# Schematic.net
KiCad netlist of a schematic drawn in Altium Designer
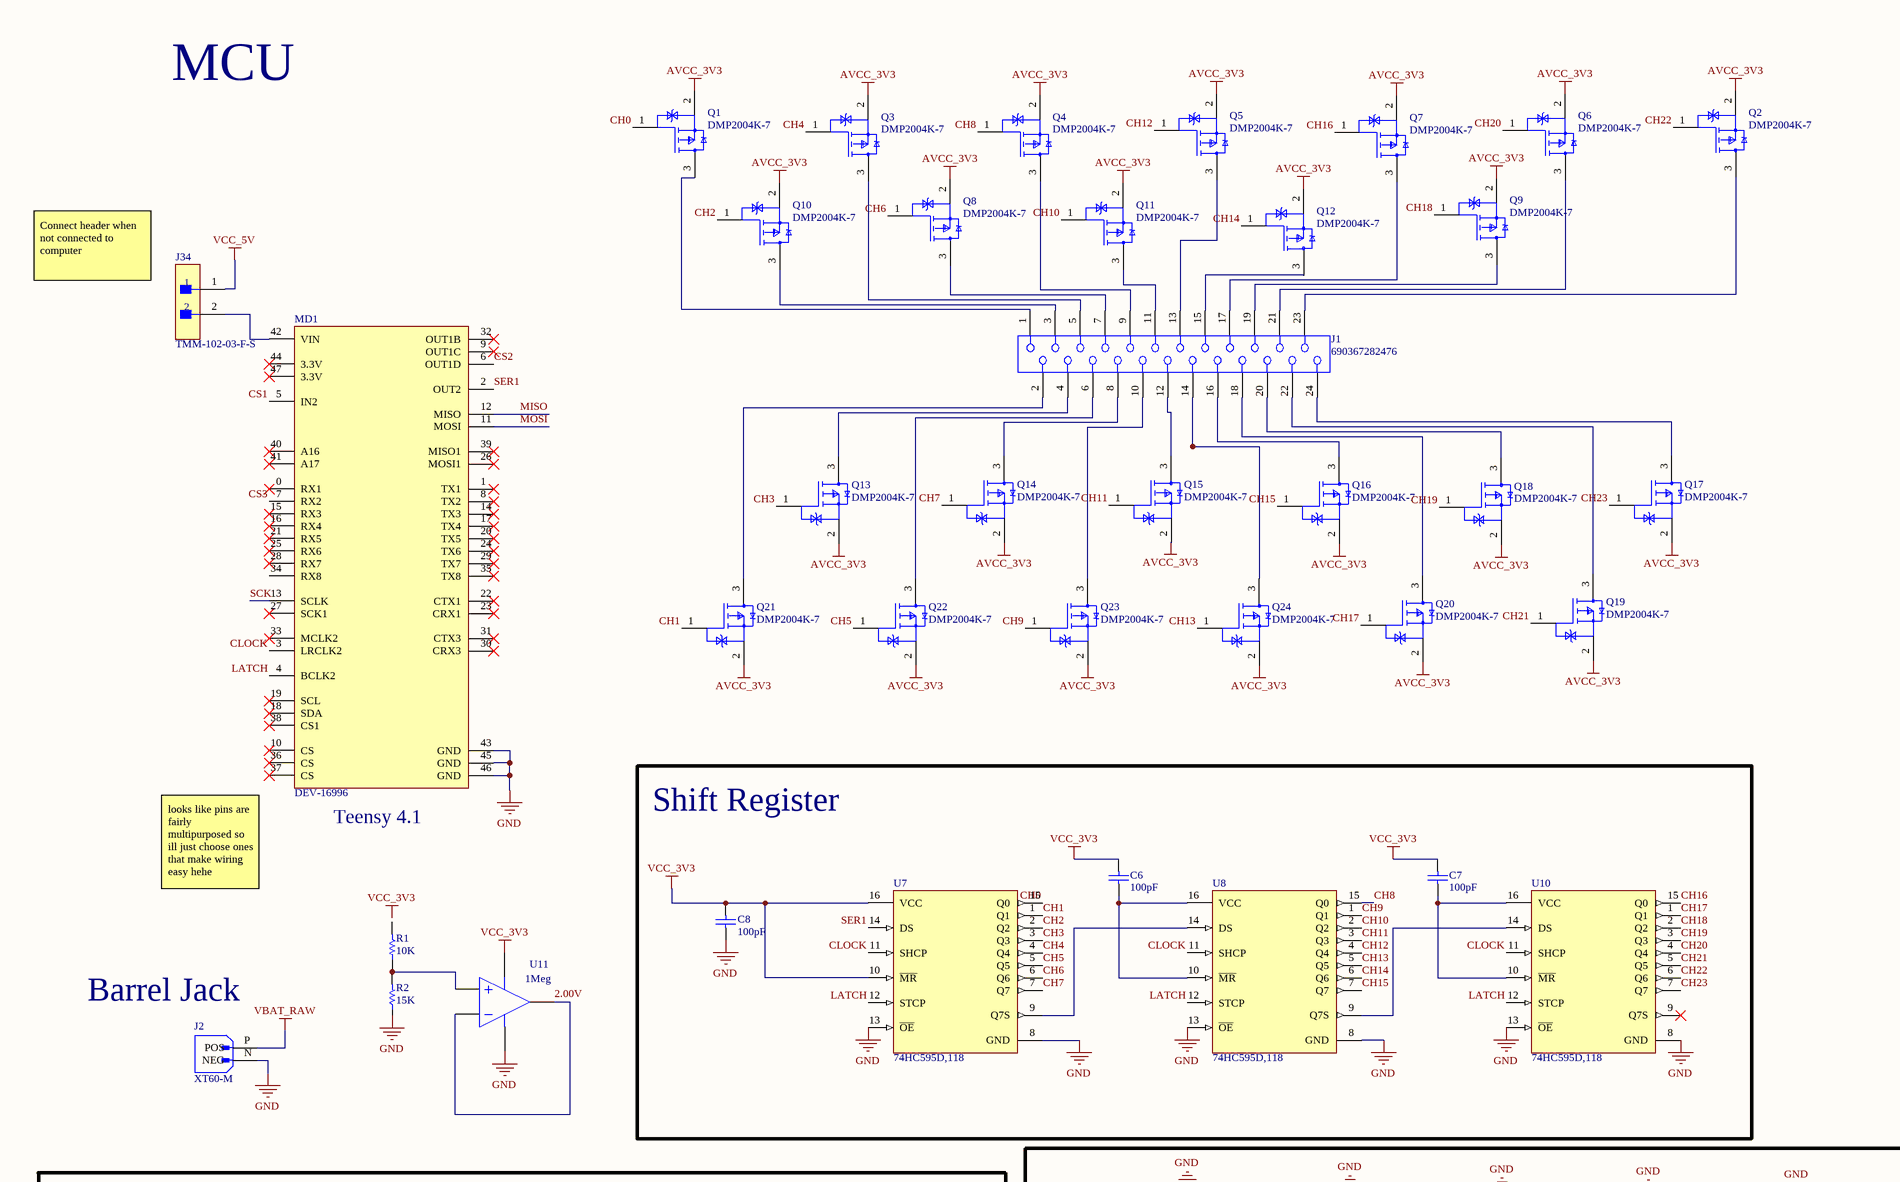
[diagram p0: Schematic.SchDoc, top left]
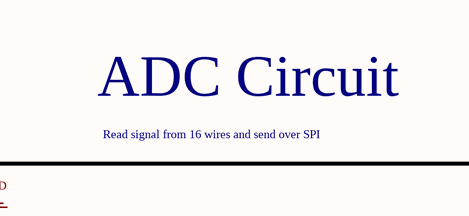
[diagram p1: Schematic.SchDoc, top right]
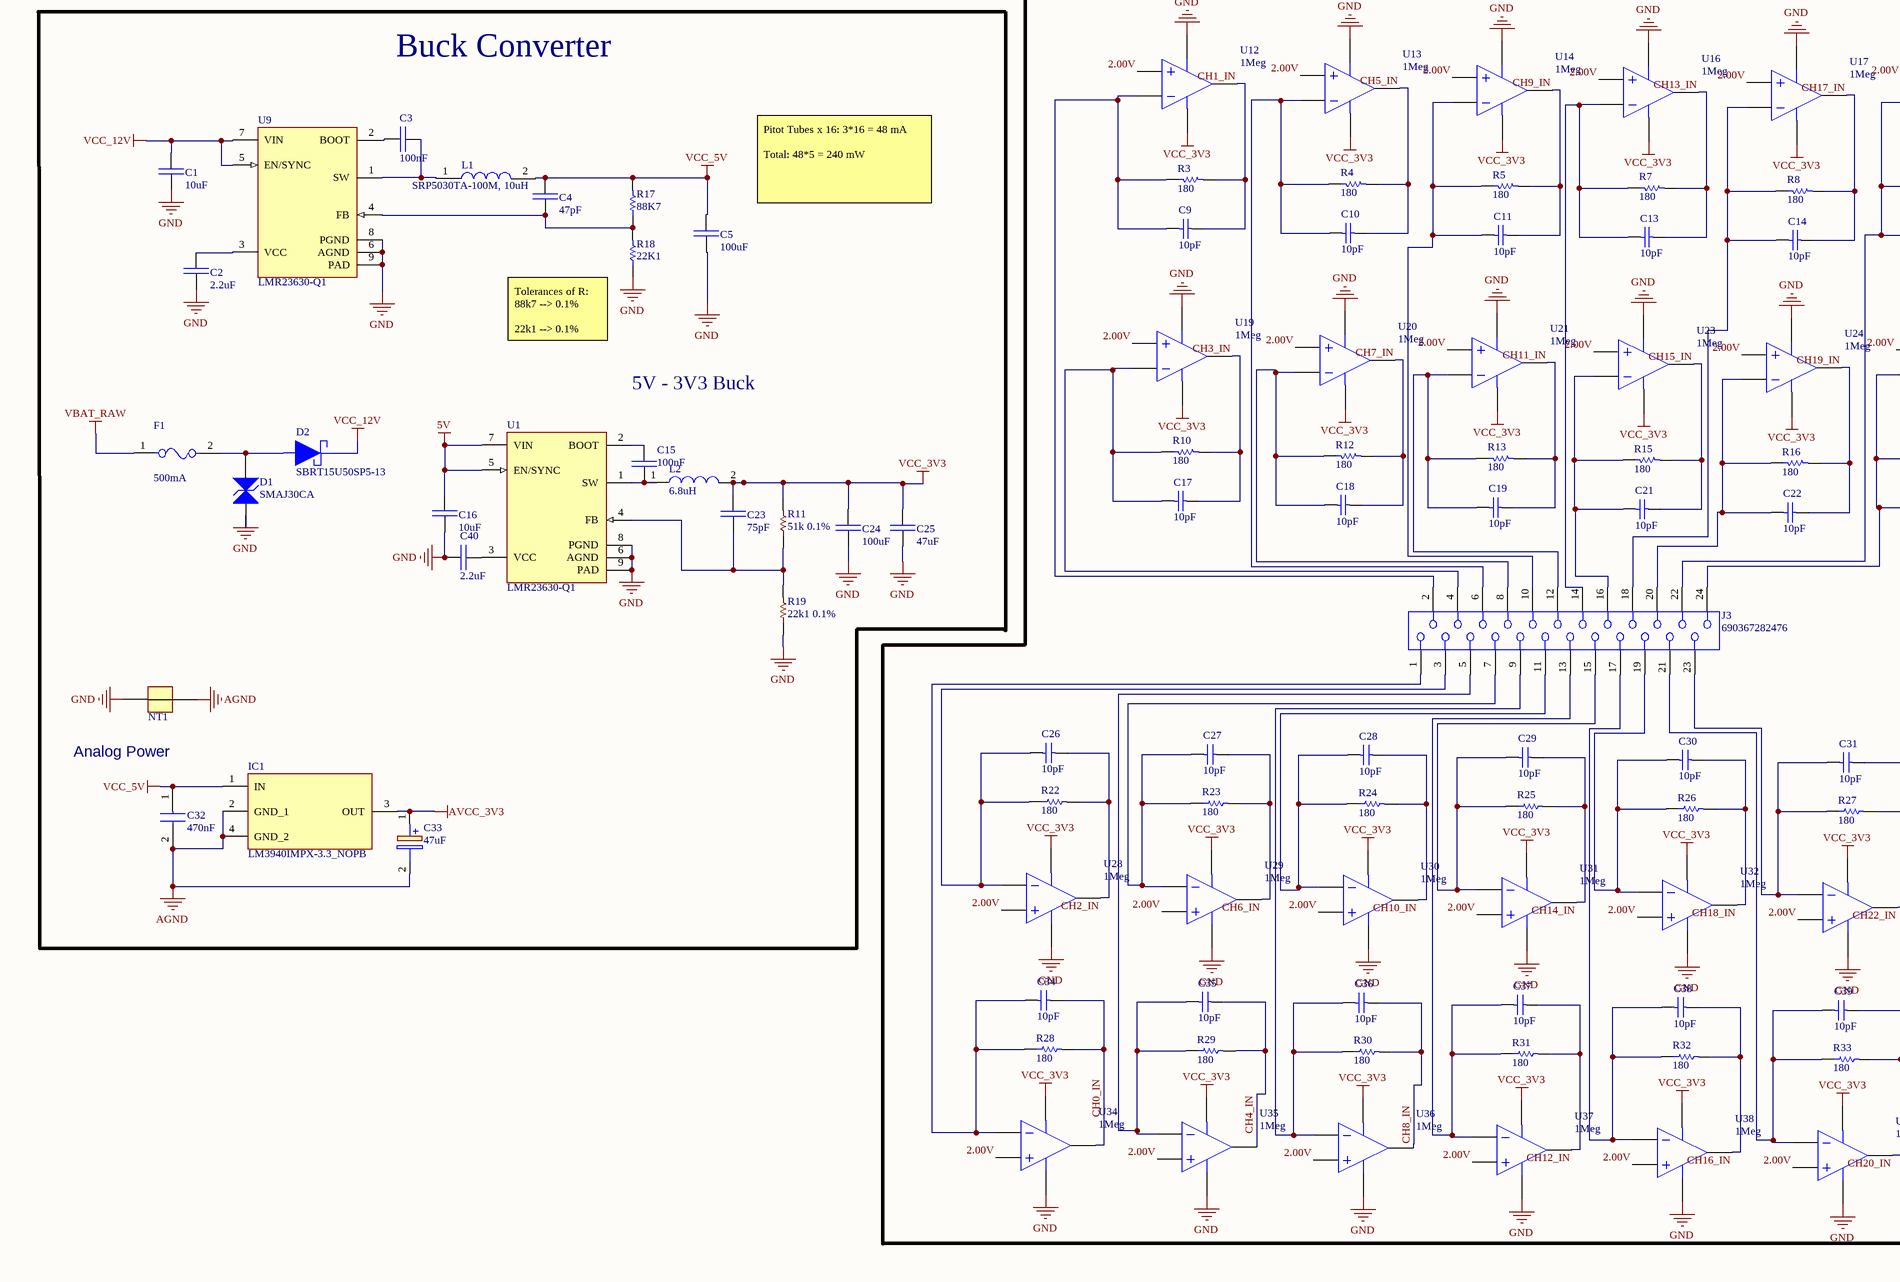
[diagram p2: Schematic.SchDoc, bottom left]
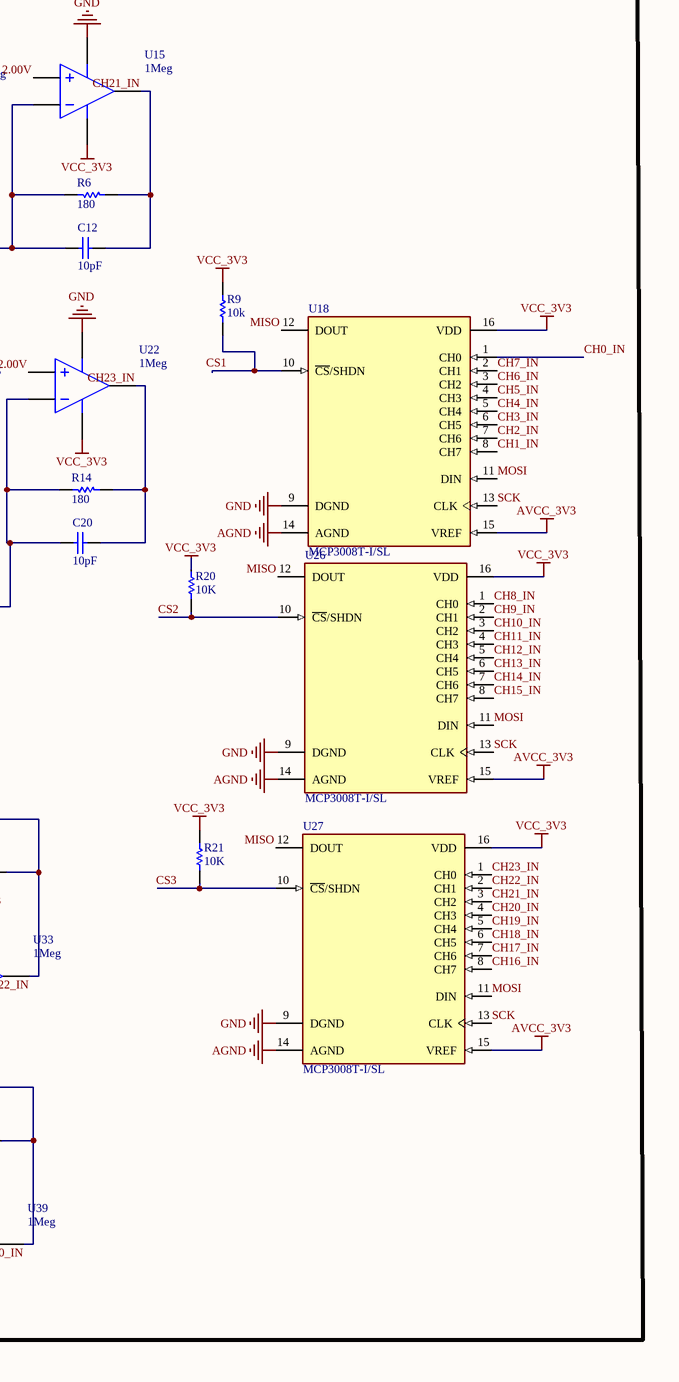
[diagram p3: Schematic.SchDoc, bottom right]

(export (version "E")
  (design (tool "Eeschema 10.0.6"))
  (components
    (comp (ref "C1")
      (value "10uF")
      (footprint "CAP_SM0603_YAGEOCC2_N")
      (fields
        (field (name "MANUFACTURER") "Murata")
        (field (name "MANUFACTURER PART NUMBER") "GRM188R6YA106MA73D")
      )
      (libsource (lib "ResistorCapsInductors") (part "GRM188R6YA106MA73D"))
    )
    (comp (ref "C2")
      (value "2.2uF")
      (footprint "CAP_SM0603_YAGEOCC2_N")
      (description "CAP CER 2.2UF 25V X5R 0603")
      (fields
        (field (name "MANUFACTURER") "Yageo")
        (field (name "MANUFACTURER PART NUMBER") "CC0603KRX7R9BB183")
      )
      (libsource (lib "ResistorCapsInductors") (part "CC0603KRX5R8BB225"))
    )
    (comp (ref "C3")
      (value "100nF")
      (footprint "CAP_SM0603_YAGEOCC2_N")
      (description "CAP 100nF SM0603 X7R 50V YAGEO CC2")
      (fields
        (field (name "MANUFACTURER") "Yageo")
        (field (name "MANUFACTURER PART NUMBER") "CC0603KRX7R9BB104")
      )
      (libsource (lib "ResistorCapsInductors") (part "CC0603KRX7R9BB104"))
    )
    (comp (ref "C4")
      (value "47pF")
      (footprint "CAP_SM0603_YAGEOCC2_N")
      (description "CAP 47pF SM0603 NPO 50V YAGEO CC2")
      (fields
        (field (name "MANUFACTURER") "Yageo")
        (field (name "MANUFACTURER PART NUMBER") "CC0603JRNPO9BN470")
      )
      (libsource (lib "ResistorCapsInductors") (part "CC0603JRNPO9BN470"))
    )
    (comp (ref "C5")
      (value "100uF")
      (footprint "FP-GRM31C-0_3-e0_3_0_8-IPC_A")
      (fields
        (field (name "MANUFACTURER") "Murata")
        (field (name "MANUFACTURER PART NUMBER") "GRM31CR61A107MEA8L")
      )
      (libsource (lib "ResistorCapsInductors") (part "GRM31CR61A107MEA8L"))
    )
    (comp (ref "C6")
      (value "100pF")
      (footprint "CAPC2013X140X50LL20T25")
      (fields
        (field (name "PART NUMBER") "0805ZC105KAZ2A")
        (field (name "MANUFACTURER") "AVX Interconnect / Elco")
      )
      (libsource (lib "Altium Content Vault") (part "CAP"))
    )
    (comp (ref "C7")
      (value "100pF")
      (footprint "CAPC2013X140X50LL20T25")
      (fields
        (field (name "PART NUMBER") "0805ZC105KAZ2A")
        (field (name "MANUFACTURER") "AVX Interconnect / Elco")
      )
      (libsource (lib "Altium Content Vault") (part "CAP"))
    )
    (comp (ref "C8")
      (value "100pF")
      (footprint "CAPC2013X140X50LL20T25")
      (fields
        (field (name "PART NUMBER") "0805ZC105KAZ2A")
        (field (name "MANUFACTURER") "AVX Interconnect / Elco")
      )
      (libsource (lib "Altium Content Vault") (part "CAP"))
    )
    (comp (ref "C9")
      (value "10pF")
      (footprint "CAP_R15_JOD")
      (description "Capacitor")
      (libsource (lib "Simulation Generic Components") (part "Capacitor"))
    )
    (comp (ref "C10")
      (value "10pF")
      (footprint "CAP_R15_JOD")
      (description "Capacitor")
      (libsource (lib "Simulation Generic Components") (part "Capacitor"))
    )
    (comp (ref "C11")
      (value "10pF")
      (footprint "CAP_R15_JOD")
      (description "Capacitor")
      (libsource (lib "Simulation Generic Components") (part "Capacitor"))
    )
    (comp (ref "C12")
      (value "10pF")
      (footprint "CAP_R15_JOD")
      (description "Capacitor")
      (libsource (lib "Simulation Generic Components") (part "Capacitor"))
    )
    (comp (ref "C13")
      (value "10pF")
      (footprint "CAP_R15_JOD")
      (description "Capacitor")
      (libsource (lib "Simulation Generic Components") (part "Capacitor"))
    )
    (comp (ref "C14")
      (value "10pF")
      (footprint "CAP_R15_JOD")
      (description "Capacitor")
      (libsource (lib "Simulation Generic Components") (part "Capacitor"))
    )
    (comp (ref "C15")
      (value "100nF")
      (footprint "CAP_SM0603_YAGEOCC2_N")
      (description "CAP 100nF SM0603 X7R 50V YAGEO CC2")
      (fields
        (field (name "MANUFACTURER") "Yageo")
        (field (name "MANUFACTURER PART NUMBER") "CC0603KRX7R9BB104")
      )
      (libsource (lib "ResistorCapsInductors") (part "CC0603KRX7R9BB104"))
    )
    (comp (ref "C16")
      (value "10uF")
      (footprint "CAP_SM0603_YAGEOCC2_N")
      (fields
        (field (name "MANUFACTURER") "Murata")
        (field (name "MANUFACTURER PART NUMBER") "GRM188R6YA106MA73D")
      )
      (libsource (lib "ResistorCapsInductors") (part "GRM188R6YA106MA73D"))
    )
    (comp (ref "C17")
      (value "10pF")
      (footprint "CAP_R15_JOD")
      (description "Capacitor")
      (libsource (lib "Simulation Generic Components") (part "Capacitor"))
    )
    (comp (ref "C18")
      (value "10pF")
      (footprint "CAP_R15_JOD")
      (description "Capacitor")
      (libsource (lib "Simulation Generic Components") (part "Capacitor"))
    )
    (comp (ref "C19")
      (value "10pF")
      (footprint "CAP_R15_JOD")
      (description "Capacitor")
      (libsource (lib "Simulation Generic Components") (part "Capacitor"))
    )
    (comp (ref "C20")
      (value "10pF")
      (footprint "CAP_R15_JOD")
      (description "Capacitor")
      (libsource (lib "Simulation Generic Components") (part "Capacitor"))
    )
    (comp (ref "C21")
      (value "10pF")
      (footprint "CAP_R15_JOD")
      (description "Capacitor")
      (libsource (lib "Simulation Generic Components") (part "Capacitor"))
    )
    (comp (ref "C22")
      (value "10pF")
      (footprint "CAP_R15_JOD")
      (description "Capacitor")
      (libsource (lib "Simulation Generic Components") (part "Capacitor"))
    )
    (comp (ref "C23")
      (value "75pF")
      (footprint "CAP_SM0603_YAGEOCC2_N")
      (description "CAP 75pF SM0603 NPO 50V YAGEO CC2")
      (fields
        (field (name "MANUFACTURER") "Yageo")
        (field (name "MANUFACTURER PART NUMBER") "CC0603JRNPO9BN820")
      )
      (libsource (lib "ResistorCapsInductors") (part "CC0603JRNPO9BN750"))
    )
    (comp (ref "C24")
      (value "100uF")
      (footprint "FP-GRM31C-0_3-e0_3_0_8-IPC_A")
      (fields
        (field (name "MANUFACTURER") "Murata")
        (field (name "MANUFACTURER PART NUMBER") "GRM31CR61A107MEA8L")
      )
      (libsource (lib "ResistorCapsInductors") (part "GRM31CR61A107MEA8L"))
    )
    (comp (ref "C25")
      (value "47uF")
      (footprint "CAP_SM0603_YAGEOCC2_N")
      (description "CAP 47uF SM0603 X5R 4V YAGEO CC2")
      (fields
        (field (name "MANUFACTURER") "Yageo")
        (field (name "MANUFACTURER PART NUMBER") "CC0603KRX7R9BB223")
      )
      (libsource (lib "ResistorCapsInductors") (part "CC0603MRX5R4BB476"))
    )
    (comp (ref "C26")
      (value "10pF")
      (footprint "CAP_R15_JOD")
      (description "Capacitor")
      (libsource (lib "Simulation Generic Components") (part "Capacitor"))
    )
    (comp (ref "C27")
      (value "10pF")
      (footprint "CAP_R15_JOD")
      (description "Capacitor")
      (libsource (lib "Simulation Generic Components") (part "Capacitor"))
    )
    (comp (ref "C28")
      (value "10pF")
      (footprint "CAP_R15_JOD")
      (description "Capacitor")
      (libsource (lib "Simulation Generic Components") (part "Capacitor"))
    )
    (comp (ref "C29")
      (value "10pF")
      (footprint "CAP_R15_JOD")
      (description "Capacitor")
      (libsource (lib "Simulation Generic Components") (part "Capacitor"))
    )
    (comp (ref "C30")
      (value "10pF")
      (footprint "CAP_R15_JOD")
      (description "Capacitor")
      (libsource (lib "Simulation Generic Components") (part "Capacitor"))
    )
    (comp (ref "C31")
      (value "10pF")
      (footprint "CAP_R15_JOD")
      (description "Capacitor")
      (libsource (lib "Simulation Generic Components") (part "Capacitor"))
    )
    (comp (ref "C32")
      (value "470nF")
      (footprint "CAPC1608X90N")
      (description "SMD/SMT CGA 0603 50V 0.47uF X7R 10% AEC-Q200")
      (fields
        (field (name "MANUFACTURER_PART_NUMBER") "CGA3E3X7R1H474K080AB")
        (field (name "MOUSER PART NUMBER") "810-CGA3E3X7R1H474KB")
      )
      (libsource (lib "ResistorCapsInductors") (part "CGA3E3X7R1H474K080AB"))
    )
    (comp (ref "C33")
      (value "47uF")
      (footprint "CAPPM3216X180N")
      (description "47uF 10V Tantalum Capacitor For LM3940IMPX-3.3_NOPB LDO")
      (fields
        (field (name "MANUFACTURER_PART_NUMBER") "TLJA476M010R0600")
        (field (name "MOUSER PART NUMBER") "581-TLJA476M010R0600")
      )
      (libsource (lib "ResistorCapsInductors") (part "TLJA476M010R0600"))
    )
    (comp (ref "C34")
      (value "10pF")
      (footprint "CAP_R15_JOD")
      (description "Capacitor")
      (libsource (lib "Simulation Generic Components") (part "Capacitor"))
    )
    (comp (ref "C35")
      (value "10pF")
      (footprint "CAP_R15_JOD")
      (description "Capacitor")
      (libsource (lib "Simulation Generic Components") (part "Capacitor"))
    )
    (comp (ref "C36")
      (value "10pF")
      (footprint "CAP_R15_JOD")
      (description "Capacitor")
      (libsource (lib "Simulation Generic Components") (part "Capacitor"))
    )
    (comp (ref "C37")
      (value "10pF")
      (footprint "CAP_R15_JOD")
      (description "Capacitor")
      (libsource (lib "Simulation Generic Components") (part "Capacitor"))
    )
    (comp (ref "C38")
      (value "10pF")
      (footprint "CAP_R15_JOD")
      (description "Capacitor")
      (libsource (lib "Simulation Generic Components") (part "Capacitor"))
    )
    (comp (ref "C39")
      (value "10pF")
      (footprint "CAP_R15_JOD")
      (description "Capacitor")
      (libsource (lib "Simulation Generic Components") (part "Capacitor"))
    )
    (comp (ref "C40")
      (value "2.2uF")
      (footprint "CAP_SM0603_YAGEOCC2_N")
      (description "CAP CER 2.2UF 25V X5R 0603")
      (fields
        (field (name "MANUFACTURER") "Yageo")
        (field (name "MANUFACTURER PART NUMBER") "CC0603KRX7R9BB183")
      )
      (libsource (lib "ResistorCapsInductors") (part "CC0603KRX5R8BB225"))
    )
    (comp (ref "D1")
      (value "SMAJ30CA")
      (footprint "LFUS-DO-214AC-A-2_V")
      (description "Transient Voltage Suppression Diode, 30 V, -65 to 150 degC, 2-Pin SMD, RoHS, Tape and Reel")
      (fields (field (name "MANUFACTURER") "Littelfuse"))
      (libsource (lib "DiodesAndFuses") (part "SMAJ30CA"))
    )
    (comp (ref "D2")
      (value "SBRT15U50SP5-13")
      (footprint "SBRT15U50SP5-13")
      (description "Reverse Polarity Protection")
      (fields (field (name "MANUFACTURER") "Diodes Incorporated"))
      (libsource (lib "DiodesAndFuses") (part "SBRT15U50SP5-13"))
    )
    (comp (ref "F1")
      (value "500mA")
      (footprint "FP-SF-0603S-MFG")
      (description "FUSE BOARD MNT 500MA 50VDC 0603")
      (fields
        (field (name "MANUFACTURER") "Bourns Inc.")
        (field (name "MANUFACTURER PART NUMBER") "SF-0603S050-2")
      )
      (libsource (lib "Altium Content Vault") (part "5bcf9b9f640e542cf0359d10258e979"))
    )
    (comp (ref "IC1")
      (value "LM3940IMPX-3.3_NOPB")
      (footprint "SOT230P700X180-4N")
      (description "3V3 LDO")
      (fields
        (field (name "MANUFACTURER_PART_NUMBER") "LM3940IMPX-3.3/NOPB")
        (field (name "MOUSER PART NUMBER") "926-LM3940IMPX33NOPB")
      )
      (libsource (lib "Power") (part "LM3940IMPX-3.3_NOPB"))
    )
    (comp (ref "J1")
      (value "690367282476")
      (footprint "FPC-SMD_24P-P0.50_05A20L24P")
      (libsource (lib "CustomParts") (part "CMP-1502-00827-2"))
    )
    (comp (ref "J2")
      (value "XT60-M")
      (footprint "AMASS_XT60-M")
      (description "Plug; DC supply; XT60; male; PIN: 2; for cable; soldered; 30A; 500V")
      (fields (field (name "MF") "AMASS"))
      (libsource (lib "XT60-M") (part "XT60-M"))
    )
    (comp (ref "J3")
      (value "690367282476")
      (footprint "FPC-SMD_24P-P0.50_05A20L24P")
      (libsource (lib "CustomParts") (part "CMP-1502-00827-2"))
    )
    (comp (ref "J34")
      (value "TMM-102-03-F-S")
      (footprint "FP-TMM-102-03-F-S-MFG")
      (description "CONN HEADER VERT 2POS 2MM")
      (libsource (lib "Altium Content Vault") (part "3bc925449376181038e59eaffc5286c"))
    )
    (comp (ref "L1")
      (value "SRP5030TA-100M, 10uH")
      (footprint "INDPM5752X300N")
      (description "10 uH Inductor")
      (fields
        (field (name "MANUFACTURER_PART_NUMBER") "SRP5030TA-100M")
        (field (name "MOUSER PART NUMBER") "652-SRP5030TA-100M")
      )
      (libsource (lib "ResistorCapsInductors") (part "SRP5030TA-100M"))
    )
    (comp (ref "L2")
      (value "6.8uH")
      (footprint "INDPM5752X300N")
      (description "6.8uH Inductor")
      (fields
        (field (name "MANUFACTURER_PART_NUMBER") "SRP5030TA-6R8M")
        (field (name "MOUSER PART NUMBER") "652-SRP5030TA-6R8M")
      )
      (libsource (lib "ResistorCapsInductors") (part "SRP5030TA-6R8M"))
    )
    (comp (ref "MD1")
      (value "DEV-16996")
      (footprint "FP-DEV-16996-MFG")
      (description "TEENSY 4.1 (HEADERS)")
      (libsource (lib "Altium Content Vault") (part "080115a1ce54750370cf87ec145ee29"))
    )
    (comp (ref "NT1")
      (value "Net Tie")
      (footprint "Net_Tie_80mil")
      (description "Use to tie together nets")
      (libsource (lib "Misc") (part "Net Tie"))
    )
    (comp (ref "Q1")
      (value "DMP2004K-7")
      (footprint "FP-SOT23-MFG")
      (description "MOSFET P-CH 20V 600MA SOT23-3")
      (fields
        (field (name "OCTOPART") "https://octopart.com/dmp2004k-7-diodes+inc.-7151877")
        (field (name "MANUFACTURER") "Diodes Inc.")
      )
      (libsource (lib "Altium Content Vault") (part "0909edbb8d389a8e80b8543cd1a9d7a"))
    )
    (comp (ref "Q2")
      (value "DMP2004K-7")
      (footprint "FP-SOT23-MFG")
      (description "MOSFET P-CH 20V 600MA SOT23-3")
      (fields
        (field (name "OCTOPART") "https://octopart.com/dmp2004k-7-diodes+inc.-7151877")
        (field (name "MANUFACTURER") "Diodes Inc.")
      )
      (libsource (lib "Altium Content Vault") (part "0909edbb8d389a8e80b8543cd1a9d7a"))
    )
    (comp (ref "Q3")
      (value "DMP2004K-7")
      (footprint "FP-SOT23-MFG")
      (description "MOSFET P-CH 20V 600MA SOT23-3")
      (fields
        (field (name "OCTOPART") "https://octopart.com/dmp2004k-7-diodes+inc.-7151877")
        (field (name "MANUFACTURER") "Diodes Inc.")
      )
      (libsource (lib "Altium Content Vault") (part "0909edbb8d389a8e80b8543cd1a9d7a"))
    )
    (comp (ref "Q4")
      (value "DMP2004K-7")
      (footprint "FP-SOT23-MFG")
      (description "MOSFET P-CH 20V 600MA SOT23-3")
      (fields
        (field (name "OCTOPART") "https://octopart.com/dmp2004k-7-diodes+inc.-7151877")
        (field (name "MANUFACTURER") "Diodes Inc.")
      )
      (libsource (lib "Altium Content Vault") (part "0909edbb8d389a8e80b8543cd1a9d7a"))
    )
    (comp (ref "Q5")
      (value "DMP2004K-7")
      (footprint "FP-SOT23-MFG")
      (description "MOSFET P-CH 20V 600MA SOT23-3")
      (fields
        (field (name "OCTOPART") "https://octopart.com/dmp2004k-7-diodes+inc.-7151877")
        (field (name "MANUFACTURER") "Diodes Inc.")
      )
      (libsource (lib "Altium Content Vault") (part "0909edbb8d389a8e80b8543cd1a9d7a"))
    )
    (comp (ref "Q6")
      (value "DMP2004K-7")
      (footprint "FP-SOT23-MFG")
      (description "MOSFET P-CH 20V 600MA SOT23-3")
      (fields
        (field (name "OCTOPART") "https://octopart.com/dmp2004k-7-diodes+inc.-7151877")
        (field (name "MANUFACTURER") "Diodes Inc.")
      )
      (libsource (lib "Altium Content Vault") (part "0909edbb8d389a8e80b8543cd1a9d7a"))
    )
    (comp (ref "Q7")
      (value "DMP2004K-7")
      (footprint "FP-SOT23-MFG")
      (description "MOSFET P-CH 20V 600MA SOT23-3")
      (fields
        (field (name "OCTOPART") "https://octopart.com/dmp2004k-7-diodes+inc.-7151877")
        (field (name "MANUFACTURER") "Diodes Inc.")
      )
      (libsource (lib "Altium Content Vault") (part "0909edbb8d389a8e80b8543cd1a9d7a"))
    )
    (comp (ref "Q8")
      (value "DMP2004K-7")
      (footprint "FP-SOT23-MFG")
      (description "MOSFET P-CH 20V 600MA SOT23-3")
      (fields
        (field (name "OCTOPART") "https://octopart.com/dmp2004k-7-diodes+inc.-7151877")
        (field (name "MANUFACTURER") "Diodes Inc.")
      )
      (libsource (lib "Altium Content Vault") (part "0909edbb8d389a8e80b8543cd1a9d7a"))
    )
    (comp (ref "Q9")
      (value "DMP2004K-7")
      (footprint "FP-SOT23-MFG")
      (description "MOSFET P-CH 20V 600MA SOT23-3")
      (fields
        (field (name "OCTOPART") "https://octopart.com/dmp2004k-7-diodes+inc.-7151877")
        (field (name "MANUFACTURER") "Diodes Inc.")
      )
      (libsource (lib "Altium Content Vault") (part "0909edbb8d389a8e80b8543cd1a9d7a"))
    )
    (comp (ref "Q10")
      (value "DMP2004K-7")
      (footprint "FP-SOT23-MFG")
      (description "MOSFET P-CH 20V 600MA SOT23-3")
      (fields
        (field (name "OCTOPART") "https://octopart.com/dmp2004k-7-diodes+inc.-7151877")
        (field (name "MANUFACTURER") "Diodes Inc.")
      )
      (libsource (lib "Altium Content Vault") (part "0909edbb8d389a8e80b8543cd1a9d7a"))
    )
    (comp (ref "Q11")
      (value "DMP2004K-7")
      (footprint "FP-SOT23-MFG")
      (description "MOSFET P-CH 20V 600MA SOT23-3")
      (fields
        (field (name "OCTOPART") "https://octopart.com/dmp2004k-7-diodes+inc.-7151877")
        (field (name "MANUFACTURER") "Diodes Inc.")
      )
      (libsource (lib "Altium Content Vault") (part "0909edbb8d389a8e80b8543cd1a9d7a"))
    )
    (comp (ref "Q12")
      (value "DMP2004K-7")
      (footprint "FP-SOT23-MFG")
      (description "MOSFET P-CH 20V 600MA SOT23-3")
      (fields
        (field (name "OCTOPART") "https://octopart.com/dmp2004k-7-diodes+inc.-7151877")
        (field (name "MANUFACTURER") "Diodes Inc.")
      )
      (libsource (lib "Altium Content Vault") (part "0909edbb8d389a8e80b8543cd1a9d7a"))
    )
    (comp (ref "Q13")
      (value "DMP2004K-7")
      (footprint "FP-SOT23-MFG")
      (description "MOSFET P-CH 20V 600MA SOT23-3")
      (fields
        (field (name "OCTOPART") "https://octopart.com/dmp2004k-7-diodes+inc.-7151877")
        (field (name "MANUFACTURER") "Diodes Inc.")
      )
      (libsource (lib "Altium Content Vault") (part "0909edbb8d389a8e80b8543cd1a9d7a"))
    )
    (comp (ref "Q14")
      (value "DMP2004K-7")
      (footprint "FP-SOT23-MFG")
      (description "MOSFET P-CH 20V 600MA SOT23-3")
      (fields
        (field (name "OCTOPART") "https://octopart.com/dmp2004k-7-diodes+inc.-7151877")
        (field (name "MANUFACTURER") "Diodes Inc.")
      )
      (libsource (lib "Altium Content Vault") (part "0909edbb8d389a8e80b8543cd1a9d7a"))
    )
    (comp (ref "Q15")
      (value "DMP2004K-7")
      (footprint "FP-SOT23-MFG")
      (description "MOSFET P-CH 20V 600MA SOT23-3")
      (fields
        (field (name "OCTOPART") "https://octopart.com/dmp2004k-7-diodes+inc.-7151877")
        (field (name "MANUFACTURER") "Diodes Inc.")
      )
      (libsource (lib "Altium Content Vault") (part "0909edbb8d389a8e80b8543cd1a9d7a"))
    )
    (comp (ref "Q16")
      (value "DMP2004K-7")
      (footprint "FP-SOT23-MFG")
      (description "MOSFET P-CH 20V 600MA SOT23-3")
      (fields
        (field (name "OCTOPART") "https://octopart.com/dmp2004k-7-diodes+inc.-7151877")
        (field (name "MANUFACTURER") "Diodes Inc.")
      )
      (libsource (lib "Altium Content Vault") (part "0909edbb8d389a8e80b8543cd1a9d7a"))
    )
    (comp (ref "Q17")
      (value "DMP2004K-7")
      (footprint "FP-SOT23-MFG")
      (description "MOSFET P-CH 20V 600MA SOT23-3")
      (fields
        (field (name "OCTOPART") "https://octopart.com/dmp2004k-7-diodes+inc.-7151877")
        (field (name "MANUFACTURER") "Diodes Inc.")
      )
      (libsource (lib "Altium Content Vault") (part "0909edbb8d389a8e80b8543cd1a9d7a"))
    )
    (comp (ref "Q18")
      (value "DMP2004K-7")
      (footprint "FP-SOT23-MFG")
      (description "MOSFET P-CH 20V 600MA SOT23-3")
      (fields
        (field (name "OCTOPART") "https://octopart.com/dmp2004k-7-diodes+inc.-7151877")
        (field (name "MANUFACTURER") "Diodes Inc.")
      )
      (libsource (lib "Altium Content Vault") (part "0909edbb8d389a8e80b8543cd1a9d7a"))
    )
    (comp (ref "Q19")
      (value "DMP2004K-7")
      (footprint "FP-SOT23-MFG")
      (description "MOSFET P-CH 20V 600MA SOT23-3")
      (fields
        (field (name "OCTOPART") "https://octopart.com/dmp2004k-7-diodes+inc.-7151877")
        (field (name "MANUFACTURER") "Diodes Inc.")
      )
      (libsource (lib "Altium Content Vault") (part "0909edbb8d389a8e80b8543cd1a9d7a"))
    )
    (comp (ref "Q20")
      (value "DMP2004K-7")
      (footprint "FP-SOT23-MFG")
      (description "MOSFET P-CH 20V 600MA SOT23-3")
      (fields
        (field (name "OCTOPART") "https://octopart.com/dmp2004k-7-diodes+inc.-7151877")
        (field (name "MANUFACTURER") "Diodes Inc.")
      )
      (libsource (lib "Altium Content Vault") (part "0909edbb8d389a8e80b8543cd1a9d7a"))
    )
    (comp (ref "Q21")
      (value "DMP2004K-7")
      (footprint "FP-SOT23-MFG")
      (description "MOSFET P-CH 20V 600MA SOT23-3")
      (fields
        (field (name "OCTOPART") "https://octopart.com/dmp2004k-7-diodes+inc.-7151877")
        (field (name "MANUFACTURER") "Diodes Inc.")
      )
      (libsource (lib "Altium Content Vault") (part "0909edbb8d389a8e80b8543cd1a9d7a"))
    )
    (comp (ref "Q22")
      (value "DMP2004K-7")
      (footprint "FP-SOT23-MFG")
      (description "MOSFET P-CH 20V 600MA SOT23-3")
      (fields
        (field (name "OCTOPART") "https://octopart.com/dmp2004k-7-diodes+inc.-7151877")
        (field (name "MANUFACTURER") "Diodes Inc.")
      )
      (libsource (lib "Altium Content Vault") (part "0909edbb8d389a8e80b8543cd1a9d7a"))
    )
    (comp (ref "Q23")
      (value "DMP2004K-7")
      (footprint "FP-SOT23-MFG")
      (description "MOSFET P-CH 20V 600MA SOT23-3")
      (fields
        (field (name "OCTOPART") "https://octopart.com/dmp2004k-7-diodes+inc.-7151877")
        (field (name "MANUFACTURER") "Diodes Inc.")
      )
      (libsource (lib "Altium Content Vault") (part "0909edbb8d389a8e80b8543cd1a9d7a"))
    )
    (comp (ref "Q24")
      (value "DMP2004K-7")
      (footprint "FP-SOT23-MFG")
      (description "MOSFET P-CH 20V 600MA SOT23-3")
      (fields
        (field (name "OCTOPART") "https://octopart.com/dmp2004k-7-diodes+inc.-7151877")
        (field (name "MANUFACTURER") "Diodes Inc.")
      )
      (libsource (lib "Altium Content Vault") (part "0909edbb8d389a8e80b8543cd1a9d7a"))
    )
    (comp (ref "R1")
      (value "10K")
      (footprint "CAP_R15_JOD")
      (description "Resistor")
      (libsource (lib "Simulation Generic Components") (part "Resistor"))
    )
    (comp (ref "R2")
      (value "15K")
      (footprint "CAP_R15_JOD")
      (description "Resistor")
      (libsource (lib "Simulation Generic Components") (part "Resistor"))
    )
    (comp (ref "R3")
      (value "180")
      (footprint "CAP_R15_JOD")
      (description "Resistor")
      (libsource (lib "Simulation Generic Components") (part "Resistor"))
    )
    (comp (ref "R4")
      (value "180")
      (footprint "CAP_R15_JOD")
      (description "Resistor")
      (libsource (lib "Simulation Generic Components") (part "Resistor"))
    )
    (comp (ref "R5")
      (value "180")
      (footprint "CAP_R15_JOD")
      (description "Resistor")
      (libsource (lib "Simulation Generic Components") (part "Resistor"))
    )
    (comp (ref "R6")
      (value "180")
      (footprint "CAP_R15_JOD")
      (description "Resistor")
      (libsource (lib "Simulation Generic Components") (part "Resistor"))
    )
    (comp (ref "R7")
      (value "180")
      (footprint "CAP_R15_JOD")
      (description "Resistor")
      (libsource (lib "Simulation Generic Components") (part "Resistor"))
    )
    (comp (ref "R8")
      (value "180")
      (footprint "CAP_R15_JOD")
      (description "Resistor")
      (libsource (lib "Simulation Generic Components") (part "Resistor"))
    )
    (comp (ref "R9")
      (value "10k")
      (footprint "CAP_R15_JOD")
      (description "Resistor")
      (libsource (lib "Simulation Generic Components") (part "Resistor"))
    )
    (comp (ref "R10")
      (value "180")
      (footprint "CAP_R15_JOD")
      (description "Resistor")
      (libsource (lib "Simulation Generic Components") (part "Resistor"))
    )
    (comp (ref "R11")
      (value "51k 0.1%")
      (footprint "RES_SM0603_YAGEORC_N")
      (description "RES 51K 0.1% SM0603 YAGEO RC_L")
      (fields
        (field (name "MANUFACTURER") "Yageo")
        (field (name "MANUFACTURER PART NUMBER") "RC0603FR-071KL")
      )
      (libsource (lib "ResistorCapsInductors") (part "RT0603BRE0751KL"))
    )
    (comp (ref "R12")
      (value "180")
      (footprint "CAP_R15_JOD")
      (description "Resistor")
      (libsource (lib "Simulation Generic Components") (part "Resistor"))
    )
    (comp (ref "R13")
      (value "180")
      (footprint "CAP_R15_JOD")
      (description "Resistor")
      (libsource (lib "Simulation Generic Components") (part "Resistor"))
    )
    (comp (ref "R14")
      (value "180")
      (footprint "CAP_R15_JOD")
      (description "Resistor")
      (libsource (lib "Simulation Generic Components") (part "Resistor"))
    )
    (comp (ref "R15")
      (value "180")
      (footprint "CAP_R15_JOD")
      (description "Resistor")
      (libsource (lib "Simulation Generic Components") (part "Resistor"))
    )
    (comp (ref "R16")
      (value "180")
      (footprint "CAP_R15_JOD")
      (description "Resistor")
      (libsource (lib "Simulation Generic Components") (part "Resistor"))
    )
    (comp (ref "R17")
      (value "88K7")
      (footprint "RES_SM0603_YAGEORC_N")
      (description "RES 88K7 SM0603 YAGEO RC_L")
      (fields
        (field (name "MANUFACTURER") "Yageo")
        (field (name "MANUFACTURER PART NUMBER") "RC0603FR-0782KL")
      )
      (libsource (lib "ResistorCapsInductors") (part "RC0603FR-0788K7L"))
    )
    (comp (ref "R18")
      (value "22K1")
      (footprint "RES_SM0603_YAGEORC_N")
      (description "RES 22K1 SM0603 YAGEO RC_L")
      (fields
        (field (name "MANUFACTURER") "Yageo")
        (field (name "MANUFACTURER PART NUMBER") "RC0603FR-0722KL")
      )
      (libsource (lib "ResistorCapsInductors") (part "RC0603FR-0722K1L"))
    )
    (comp (ref "R19")
      (value "22k1 0.1%")
      (footprint "RES_SM0603_YAGEORC_N")
      (description "RES 22K1 0.1% SM0603 YAGEO RC_L")
      (fields
        (field (name "MANUFACTURER") "Yageo")
        (field (name "MANUFACTURER PART NUMBER") "RC0603FR-071KL")
      )
      (libsource (lib "ResistorCapsInductors") (part "RT0603BRD0722K1L"))
    )
    (comp (ref "R20")
      (value "10K")
      (footprint "CAP_R15_JOD")
      (description "Resistor")
      (libsource (lib "Simulation Generic Components") (part "Resistor"))
    )
    (comp (ref "R21")
      (value "10K")
      (footprint "CAP_R15_JOD")
      (description "Resistor")
      (libsource (lib "Simulation Generic Components") (part "Resistor"))
    )
    (comp (ref "R22")
      (value "180")
      (footprint "CAP_R15_JOD")
      (description "Resistor")
      (libsource (lib "Simulation Generic Components") (part "Resistor"))
    )
    (comp (ref "R23")
      (value "180")
      (footprint "CAP_R15_JOD")
      (description "Resistor")
      (libsource (lib "Simulation Generic Components") (part "Resistor"))
    )
    (comp (ref "R24")
      (value "180")
      (footprint "CAP_R15_JOD")
      (description "Resistor")
      (libsource (lib "Simulation Generic Components") (part "Resistor"))
    )
    (comp (ref "R25")
      (value "180")
      (footprint "CAP_R15_JOD")
      (description "Resistor")
      (libsource (lib "Simulation Generic Components") (part "Resistor"))
    )
    (comp (ref "R26")
      (value "180")
      (footprint "CAP_R15_JOD")
      (description "Resistor")
      (libsource (lib "Simulation Generic Components") (part "Resistor"))
    )
    (comp (ref "R27")
      (value "180")
      (footprint "CAP_R15_JOD")
      (description "Resistor")
      (libsource (lib "Simulation Generic Components") (part "Resistor"))
    )
    (comp (ref "R28")
      (value "180")
      (footprint "CAP_R15_JOD")
      (description "Resistor")
      (libsource (lib "Simulation Generic Components") (part "Resistor"))
    )
    (comp (ref "R29")
      (value "180")
      (footprint "CAP_R15_JOD")
      (description "Resistor")
      (libsource (lib "Simulation Generic Components") (part "Resistor"))
    )
    (comp (ref "R30")
      (value "180")
      (footprint "CAP_R15_JOD")
      (description "Resistor")
      (libsource (lib "Simulation Generic Components") (part "Resistor"))
    )
    (comp (ref "R31")
      (value "180")
      (footprint "CAP_R15_JOD")
      (description "Resistor")
      (libsource (lib "Simulation Generic Components") (part "Resistor"))
    )
    (comp (ref "R32")
      (value "180")
      (footprint "CAP_R15_JOD")
      (description "Resistor")
      (libsource (lib "Simulation Generic Components") (part "Resistor"))
    )
    (comp (ref "R33")
      (value "180")
      (footprint "CAP_R15_JOD")
      (description "Resistor")
      (libsource (lib "Simulation Generic Components") (part "Resistor"))
    )
    (comp (ref "U1")
      (value "LMR23630-Q1")
      (footprint "DDA0008E_N")
      (description "Buck Converter")
      (libsource (lib "Power") (part "LMR23630-Q1"))
    )
    (comp (ref "U7")
      (value "74HC595D,118")
      (footprint "FP-SOT109-1-IPC_C")
      (description "IC SHIFT REGISTER 8BIT 16SOIC")
      (libsource (lib "Altium Content Vault") (part "7b153f231cfcc3ac06dee253bd56617"))
    )
    (comp (ref "U8")
      (value "74HC595D,118")
      (footprint "FP-SOT109-1-IPC_C")
      (description "IC SHIFT REGISTER 8BIT 16SOIC")
      (libsource (lib "Altium Content Vault") (part "7b153f231cfcc3ac06dee253bd56617"))
    )
    (comp (ref "U9")
      (value "LMR23630-Q1")
      (footprint "DDA0008E_N")
      (description "Buck Converter")
      (libsource (lib "Power") (part "LMR23630-Q1"))
    )
    (comp (ref "U10")
      (value "74HC595D,118")
      (footprint "FP-SOT109-1-IPC_C")
      (description "IC SHIFT REGISTER 8BIT 16SOIC")
      (libsource (lib "Altium Content Vault") (part "7b153f231cfcc3ac06dee253bd56617"))
    )
    (comp (ref "U11")
      (value "Ideal Operational Amplifier")
      (footprint "DCK0005A-IPC_B")
      (fields (field (name "GAIN") "1Meg"))
      (libsource (lib "Simulation Generic Components") (part "OpAmp with power terminals"))
    )
    (comp (ref "U12")
      (value "Ideal Operational Amplifier")
      (footprint "DCK0005A-IPC_B")
      (fields (field (name "GAIN") "1Meg"))
      (libsource (lib "Simulation Generic Components") (part "OpAmp with power terminals"))
    )
    (comp (ref "U13")
      (value "Ideal Operational Amplifier")
      (footprint "DCK0005A-IPC_B")
      (fields (field (name "GAIN") "1Meg"))
      (libsource (lib "Simulation Generic Components") (part "OpAmp with power terminals"))
    )
    (comp (ref "U14")
      (value "Ideal Operational Amplifier")
      (footprint "DCK0005A-IPC_B")
      (fields (field (name "GAIN") "1Meg"))
      (libsource (lib "Simulation Generic Components") (part "OpAmp with power terminals"))
    )
    (comp (ref "U15")
      (value "Ideal Operational Amplifier")
      (footprint "DCK0005A-IPC_B")
      (fields (field (name "GAIN") "1Meg"))
      (libsource (lib "Simulation Generic Components") (part "OpAmp with power terminals"))
    )
    (comp (ref "U16")
      (value "Ideal Operational Amplifier")
      (footprint "DCK0005A-IPC_B")
      (fields (field (name "GAIN") "1Meg"))
      (libsource (lib "Simulation Generic Components") (part "OpAmp with power terminals"))
    )
    (comp (ref "U17")
      (value "Ideal Operational Amplifier")
      (footprint "DCK0005A-IPC_B")
      (fields (field (name "GAIN") "1Meg"))
      (libsource (lib "Simulation Generic Components") (part "OpAmp with power terminals"))
    )
    (comp (ref "U18")
      (value "MCP3008T-I/SL")
      (footprint "FP-C04-108-MFG")
      (description "IC ADC 10BIT SAR 16SOIC")
      (libsource (lib "Altium Content Vault") (part "049cb4bd9558e05d9b89494b6be139f"))
    )
    (comp (ref "U19")
      (value "Ideal Operational Amplifier")
      (footprint "DCK0005A-IPC_B")
      (fields (field (name "GAIN") "1Meg"))
      (libsource (lib "Simulation Generic Components") (part "OpAmp with power terminals"))
    )
    (comp (ref "U20")
      (value "Ideal Operational Amplifier")
      (footprint "DCK0005A-IPC_B")
      (fields (field (name "GAIN") "1Meg"))
      (libsource (lib "Simulation Generic Components") (part "OpAmp with power terminals"))
    )
    (comp (ref "U21")
      (value "Ideal Operational Amplifier")
      (footprint "DCK0005A-IPC_B")
      (fields (field (name "GAIN") "1Meg"))
      (libsource (lib "Simulation Generic Components") (part "OpAmp with power terminals"))
    )
    (comp (ref "U22")
      (value "Ideal Operational Amplifier")
      (footprint "DCK0005A-IPC_B")
      (fields (field (name "GAIN") "1Meg"))
      (libsource (lib "Simulation Generic Components") (part "OpAmp with power terminals"))
    )
    (comp (ref "U23")
      (value "Ideal Operational Amplifier")
      (footprint "DCK0005A-IPC_B")
      (fields (field (name "GAIN") "1Meg"))
      (libsource (lib "Simulation Generic Components") (part "OpAmp with power terminals"))
    )
    (comp (ref "U24")
      (value "Ideal Operational Amplifier")
      (footprint "DCK0005A-IPC_B")
      (fields (field (name "GAIN") "1Meg"))
      (libsource (lib "Simulation Generic Components") (part "OpAmp with power terminals"))
    )
    (comp (ref "U26")
      (value "MCP3008T-I/SL")
      (footprint "FP-C04-108-MFG")
      (description "IC ADC 10BIT SAR 16SOIC")
      (libsource (lib "Altium Content Vault") (part "049cb4bd9558e05d9b89494b6be139f"))
    )
    (comp (ref "U27")
      (value "MCP3008T-I/SL")
      (footprint "FP-C04-108-MFG")
      (description "IC ADC 10BIT SAR 16SOIC")
      (libsource (lib "Altium Content Vault") (part "049cb4bd9558e05d9b89494b6be139f"))
    )
    (comp (ref "U28")
      (value "Ideal Operational Amplifier")
      (footprint "DCK0005A-IPC_B")
      (fields (field (name "GAIN") "1Meg"))
      (libsource (lib "Simulation Generic Components") (part "OpAmp with power terminals"))
    )
    (comp (ref "U29")
      (value "Ideal Operational Amplifier")
      (footprint "DCK0005A-IPC_B")
      (fields (field (name "GAIN") "1Meg"))
      (libsource (lib "Simulation Generic Components") (part "OpAmp with power terminals"))
    )
    (comp (ref "U30")
      (value "Ideal Operational Amplifier")
      (footprint "DCK0005A-IPC_B")
      (fields (field (name "GAIN") "1Meg"))
      (libsource (lib "Simulation Generic Components") (part "OpAmp with power terminals"))
    )
    (comp (ref "U31")
      (value "Ideal Operational Amplifier")
      (footprint "DCK0005A-IPC_B")
      (fields (field (name "GAIN") "1Meg"))
      (libsource (lib "Simulation Generic Components") (part "OpAmp with power terminals"))
    )
    (comp (ref "U32")
      (value "Ideal Operational Amplifier")
      (footprint "DCK0005A-IPC_B")
      (fields (field (name "GAIN") "1Meg"))
      (libsource (lib "Simulation Generic Components") (part "OpAmp with power terminals"))
    )
    (comp (ref "U33")
      (value "Ideal Operational Amplifier")
      (footprint "DCK0005A-IPC_B")
      (fields (field (name "GAIN") "1Meg"))
      (libsource (lib "Simulation Generic Components") (part "OpAmp with power terminals"))
    )
    (comp (ref "U34")
      (value "Ideal Operational Amplifier")
      (footprint "DCK0005A-IPC_B")
      (fields (field (name "GAIN") "1Meg"))
      (libsource (lib "Simulation Generic Components") (part "OpAmp with power terminals"))
    )
    (comp (ref "U35")
      (value "Ideal Operational Amplifier")
      (footprint "DCK0005A-IPC_B")
      (fields (field (name "GAIN") "1Meg"))
      (libsource (lib "Simulation Generic Components") (part "OpAmp with power terminals"))
    )
    (comp (ref "U36")
      (value "Ideal Operational Amplifier")
      (footprint "DCK0005A-IPC_B")
      (fields (field (name "GAIN") "1Meg"))
      (libsource (lib "Simulation Generic Components") (part "OpAmp with power terminals"))
    )
    (comp (ref "U37")
      (value "Ideal Operational Amplifier")
      (footprint "DCK0005A-IPC_B")
      (fields (field (name "GAIN") "1Meg"))
      (libsource (lib "Simulation Generic Components") (part "OpAmp with power terminals"))
    )
    (comp (ref "U38")
      (value "Ideal Operational Amplifier")
      (footprint "DCK0005A-IPC_B")
      (fields (field (name "GAIN") "1Meg"))
      (libsource (lib "Simulation Generic Components") (part "OpAmp with power terminals"))
    )
    (comp (ref "U39")
      (value "Ideal Operational Amplifier")
      (footprint "DCK0005A-IPC_B")
      (fields (field (name "GAIN") "1Meg"))
      (libsource (lib "Simulation Generic Components") (part "OpAmp with power terminals"))
    )
  )
  (nets
    (net (code "1") (name "/2.00V") (class "Default")
      (node (ref "U12") (pin "2") (pinfunction "IN+_2") (pintype "passive"))
      (node (ref "U13") (pin "2") (pinfunction "IN+_2") (pintype "passive"))
      (node (ref "U14") (pin "2") (pinfunction "IN+_2") (pintype "passive"))
      (node (ref "U15") (pin "2") (pinfunction "IN+_2") (pintype "passive"))
      (node (ref "U16") (pin "2") (pinfunction "IN+_2") (pintype "passive"))
      (node (ref "U17") (pin "2") (pinfunction "IN+_2") (pintype "passive"))
      (node (ref "U19") (pin "2") (pinfunction "IN+_2") (pintype "passive"))
      (node (ref "U20") (pin "2") (pinfunction "IN+_2") (pintype "passive"))
      (node (ref "U21") (pin "2") (pinfunction "IN+_2") (pintype "passive"))
      (node (ref "U22") (pin "2") (pinfunction "IN+_2") (pintype "passive"))
      (node (ref "U23") (pin "2") (pinfunction "IN+_2") (pintype "passive"))
      (node (ref "U24") (pin "2") (pinfunction "IN+_2") (pintype "passive"))
      (node (ref "U28") (pin "2") (pinfunction "IN+_2") (pintype "passive"))
      (node (ref "U29") (pin "2") (pinfunction "IN+_2") (pintype "passive"))
      (node (ref "U30") (pin "2") (pinfunction "IN+_2") (pintype "passive"))
      (node (ref "U31") (pin "2") (pinfunction "IN+_2") (pintype "passive"))
      (node (ref "U32") (pin "2") (pinfunction "IN+_2") (pintype "passive"))
      (node (ref "U33") (pin "2") (pinfunction "IN+_2") (pintype "passive"))
      (node (ref "U34") (pin "2") (pinfunction "IN+_2") (pintype "passive"))
      (node (ref "U35") (pin "2") (pinfunction "IN+_2") (pintype "passive"))
      (node (ref "U36") (pin "2") (pinfunction "IN+_2") (pintype "passive"))
      (node (ref "U37") (pin "2") (pinfunction "IN+_2") (pintype "passive"))
      (node (ref "U38") (pin "2") (pinfunction "IN+_2") (pintype "passive"))
      (node (ref "U39") (pin "2") (pinfunction "IN+_2") (pintype "passive"))
    )
    (net (code "2") (name "/CH0") (class "Default")
      (node (ref "Q1") (pin "1") (pinfunction "G_1") (pintype "passive"))
      (node (ref "U7") (pin "15") (pinfunction "Q0_15") (pintype "output"))
    )
    (net (code "3") (name "/CH0_IN") (class "Default")
      (node (ref "C34") (pin "2") (pinfunction "2_2") (pintype "passive"))
      (node (ref "R28") (pin "2") (pinfunction "2_2") (pintype "passive"))
      (node (ref "U18") (pin "1") (pinfunction "CH0_1") (pintype "input"))
      (node (ref "U34") (pin "3") (pinfunction "OUT_3") (pintype "passive"))
    )
    (net (code "4") (name "/CH1") (class "Default")
      (node (ref "Q21") (pin "1") (pinfunction "G_1") (pintype "passive"))
      (node (ref "U7") (pin "1") (pinfunction "Q1_1") (pintype "output"))
    )
    (net (code "5") (name "/CH1_IN") (class "Default")
      (node (ref "C9") (pin "2") (pinfunction "2_2") (pintype "passive"))
      (node (ref "R3") (pin "2") (pinfunction "2_2") (pintype "passive"))
      (node (ref "U12") (pin "3") (pinfunction "OUT_3") (pintype "passive"))
      (node (ref "U18") (pin "8") (pinfunction "CH7_8") (pintype "input"))
    )
    (net (code "6") (name "/CH2") (class "Default")
      (node (ref "Q10") (pin "1") (pinfunction "G_1") (pintype "passive"))
      (node (ref "U7") (pin "2") (pinfunction "Q2_2") (pintype "output"))
    )
    (net (code "7") (name "/CH2_IN") (class "Default")
      (node (ref "C26") (pin "2") (pinfunction "2_2") (pintype "passive"))
      (node (ref "R22") (pin "2") (pinfunction "2_2") (pintype "passive"))
      (node (ref "U18") (pin "7") (pinfunction "CH6_7") (pintype "input"))
      (node (ref "U28") (pin "3") (pinfunction "OUT_3") (pintype "passive"))
    )
    (net (code "8") (name "/CH3") (class "Default")
      (node (ref "Q13") (pin "1") (pinfunction "G_1") (pintype "passive"))
      (node (ref "U7") (pin "3") (pinfunction "Q3_3") (pintype "output"))
    )
    (net (code "9") (name "/CH3_IN") (class "Default")
      (node (ref "C17") (pin "2") (pinfunction "2_2") (pintype "passive"))
      (node (ref "R10") (pin "2") (pinfunction "2_2") (pintype "passive"))
      (node (ref "U18") (pin "6") (pinfunction "CH5_6") (pintype "input"))
      (node (ref "U19") (pin "3") (pinfunction "OUT_3") (pintype "passive"))
    )
    (net (code "10") (name "/CH4") (class "Default")
      (node (ref "Q3") (pin "1") (pinfunction "G_1") (pintype "passive"))
      (node (ref "U7") (pin "4") (pinfunction "Q4_4") (pintype "output"))
    )
    (net (code "11") (name "/CH4_IN") (class "Default")
      (node (ref "C35") (pin "2") (pinfunction "2_2") (pintype "passive"))
      (node (ref "R29") (pin "2") (pinfunction "2_2") (pintype "passive"))
      (node (ref "U18") (pin "5") (pinfunction "CH4_5") (pintype "input"))
      (node (ref "U35") (pin "3") (pinfunction "OUT_3") (pintype "passive"))
    )
    (net (code "12") (name "/CH5") (class "Default")
      (node (ref "Q22") (pin "1") (pinfunction "G_1") (pintype "passive"))
      (node (ref "U7") (pin "5") (pinfunction "Q5_5") (pintype "output"))
    )
    (net (code "13") (name "/CH5_IN") (class "Default")
      (node (ref "C10") (pin "2") (pinfunction "2_2") (pintype "passive"))
      (node (ref "R4") (pin "2") (pinfunction "2_2") (pintype "passive"))
      (node (ref "U13") (pin "3") (pinfunction "OUT_3") (pintype "passive"))
      (node (ref "U18") (pin "4") (pinfunction "CH3_4") (pintype "input"))
    )
    (net (code "14") (name "/CH6") (class "Default")
      (node (ref "Q8") (pin "1") (pinfunction "G_1") (pintype "passive"))
      (node (ref "U7") (pin "6") (pinfunction "Q6_6") (pintype "output"))
    )
    (net (code "15") (name "/CH6_IN") (class "Default")
      (node (ref "C27") (pin "2") (pinfunction "2_2") (pintype "passive"))
      (node (ref "R23") (pin "2") (pinfunction "2_2") (pintype "passive"))
      (node (ref "U18") (pin "3") (pinfunction "CH2_3") (pintype "input"))
      (node (ref "U29") (pin "3") (pinfunction "OUT_3") (pintype "passive"))
    )
    (net (code "16") (name "/CH7") (class "Default")
      (node (ref "Q14") (pin "1") (pinfunction "G_1") (pintype "passive"))
      (node (ref "U7") (pin "7") (pinfunction "Q7_7") (pintype "output"))
    )
    (net (code "17") (name "/CH7_IN") (class "Default")
      (node (ref "C18") (pin "2") (pinfunction "2_2") (pintype "passive"))
      (node (ref "R12") (pin "2") (pinfunction "2_2") (pintype "passive"))
      (node (ref "U18") (pin "2") (pinfunction "CH1_2") (pintype "input"))
      (node (ref "U20") (pin "3") (pinfunction "OUT_3") (pintype "passive"))
    )
    (net (code "18") (name "/CH8") (class "Default")
      (node (ref "Q4") (pin "1") (pinfunction "G_1") (pintype "passive"))
      (node (ref "U8") (pin "15") (pinfunction "Q0_15") (pintype "output"))
    )
    (net (code "19") (name "/CH8_IN") (class "Default")
      (node (ref "C36") (pin "2") (pinfunction "2_2") (pintype "passive"))
      (node (ref "R30") (pin "2") (pinfunction "2_2") (pintype "passive"))
      (node (ref "U26") (pin "1") (pinfunction "CH0_1") (pintype "input"))
      (node (ref "U36") (pin "3") (pinfunction "OUT_3") (pintype "passive"))
    )
    (net (code "20") (name "/CH9") (class "Default")
      (node (ref "Q23") (pin "1") (pinfunction "G_1") (pintype "passive"))
      (node (ref "U8") (pin "1") (pinfunction "Q1_1") (pintype "output"))
    )
    (net (code "21") (name "/CH9_IN") (class "Default")
      (node (ref "C11") (pin "2") (pinfunction "2_2") (pintype "passive"))
      (node (ref "R5") (pin "2") (pinfunction "2_2") (pintype "passive"))
      (node (ref "U14") (pin "3") (pinfunction "OUT_3") (pintype "passive"))
      (node (ref "U26") (pin "2") (pinfunction "CH1_2") (pintype "input"))
    )
    (net (code "22") (name "/CH10") (class "Default")
      (node (ref "Q11") (pin "1") (pinfunction "G_1") (pintype "passive"))
      (node (ref "U8") (pin "2") (pinfunction "Q2_2") (pintype "output"))
    )
    (net (code "23") (name "/CH10_IN") (class "Default")
      (node (ref "C28") (pin "2") (pinfunction "2_2") (pintype "passive"))
      (node (ref "R24") (pin "2") (pinfunction "2_2") (pintype "passive"))
      (node (ref "U26") (pin "3") (pinfunction "CH2_3") (pintype "input"))
      (node (ref "U30") (pin "3") (pinfunction "OUT_3") (pintype "passive"))
    )
    (net (code "24") (name "/CH11") (class "Default")
      (node (ref "Q15") (pin "1") (pinfunction "G_1") (pintype "passive"))
      (node (ref "U8") (pin "3") (pinfunction "Q3_3") (pintype "output"))
    )
    (net (code "25") (name "/CH11_IN") (class "Default")
      (node (ref "C19") (pin "2") (pinfunction "2_2") (pintype "passive"))
      (node (ref "R13") (pin "2") (pinfunction "2_2") (pintype "passive"))
      (node (ref "U21") (pin "3") (pinfunction "OUT_3") (pintype "passive"))
      (node (ref "U26") (pin "4") (pinfunction "CH3_4") (pintype "input"))
    )
    (net (code "26") (name "/CH12") (class "Default")
      (node (ref "Q5") (pin "1") (pinfunction "G_1") (pintype "passive"))
      (node (ref "U8") (pin "4") (pinfunction "Q4_4") (pintype "output"))
    )
    (net (code "27") (name "/CH12_IN") (class "Default")
      (node (ref "C37") (pin "2") (pinfunction "2_2") (pintype "passive"))
      (node (ref "R31") (pin "2") (pinfunction "2_2") (pintype "passive"))
      (node (ref "U26") (pin "5") (pinfunction "CH4_5") (pintype "input"))
      (node (ref "U37") (pin "3") (pinfunction "OUT_3") (pintype "passive"))
    )
    (net (code "28") (name "/CH13") (class "Default")
      (node (ref "Q24") (pin "1") (pinfunction "G_1") (pintype "passive"))
      (node (ref "U8") (pin "5") (pinfunction "Q5_5") (pintype "output"))
    )
    (net (code "29") (name "/CH13_IN") (class "Default")
      (node (ref "C13") (pin "2") (pinfunction "2_2") (pintype "passive"))
      (node (ref "R7") (pin "2") (pinfunction "2_2") (pintype "passive"))
      (node (ref "U16") (pin "3") (pinfunction "OUT_3") (pintype "passive"))
      (node (ref "U26") (pin "6") (pinfunction "CH5_6") (pintype "input"))
    )
    (net (code "30") (name "/CH14") (class "Default")
      (node (ref "Q12") (pin "1") (pinfunction "G_1") (pintype "passive"))
      (node (ref "U8") (pin "6") (pinfunction "Q6_6") (pintype "output"))
    )
    (net (code "31") (name "/CH14_IN") (class "Default")
      (node (ref "C29") (pin "2") (pinfunction "2_2") (pintype "passive"))
      (node (ref "R25") (pin "2") (pinfunction "2_2") (pintype "passive"))
      (node (ref "U26") (pin "7") (pinfunction "CH6_7") (pintype "input"))
      (node (ref "U31") (pin "3") (pinfunction "OUT_3") (pintype "passive"))
    )
    (net (code "32") (name "/CH15") (class "Default")
      (node (ref "Q16") (pin "1") (pinfunction "G_1") (pintype "passive"))
      (node (ref "U8") (pin "7") (pinfunction "Q7_7") (pintype "output"))
    )
    (net (code "33") (name "/CH15_IN") (class "Default")
      (node (ref "C21") (pin "2") (pinfunction "2_2") (pintype "passive"))
      (node (ref "R15") (pin "2") (pinfunction "2_2") (pintype "passive"))
      (node (ref "U23") (pin "3") (pinfunction "OUT_3") (pintype "passive"))
      (node (ref "U26") (pin "8") (pinfunction "CH7_8") (pintype "input"))
    )
    (net (code "34") (name "/CH16") (class "Default")
      (node (ref "Q7") (pin "1") (pinfunction "G_1") (pintype "passive"))
      (node (ref "U10") (pin "15") (pinfunction "Q0_15") (pintype "output"))
    )
    (net (code "35") (name "/CH16_IN") (class "Default")
      (node (ref "C38") (pin "2") (pinfunction "2_2") (pintype "passive"))
      (node (ref "R32") (pin "2") (pinfunction "2_2") (pintype "passive"))
      (node (ref "U27") (pin "8") (pinfunction "CH7_8") (pintype "input"))
      (node (ref "U38") (pin "3") (pinfunction "OUT_3") (pintype "passive"))
    )
    (net (code "36") (name "/CH17") (class "Default")
      (node (ref "Q20") (pin "1") (pinfunction "G_1") (pintype "passive"))
      (node (ref "U10") (pin "1") (pinfunction "Q1_1") (pintype "output"))
    )
    (net (code "37") (name "/CH17_IN") (class "Default")
      (node (ref "C14") (pin "2") (pinfunction "2_2") (pintype "passive"))
      (node (ref "R8") (pin "2") (pinfunction "2_2") (pintype "passive"))
      (node (ref "U17") (pin "3") (pinfunction "OUT_3") (pintype "passive"))
      (node (ref "U27") (pin "7") (pinfunction "CH6_7") (pintype "input"))
    )
    (net (code "38") (name "/CH18") (class "Default")
      (node (ref "Q9") (pin "1") (pinfunction "G_1") (pintype "passive"))
      (node (ref "U10") (pin "2") (pinfunction "Q2_2") (pintype "output"))
    )
    (net (code "39") (name "/CH18_IN") (class "Default")
      (node (ref "C30") (pin "2") (pinfunction "2_2") (pintype "passive"))
      (node (ref "R26") (pin "2") (pinfunction "2_2") (pintype "passive"))
      (node (ref "U27") (pin "6") (pinfunction "CH5_6") (pintype "input"))
      (node (ref "U32") (pin "3") (pinfunction "OUT_3") (pintype "passive"))
    )
    (net (code "40") (name "/CH19") (class "Default")
      (node (ref "Q18") (pin "1") (pinfunction "G_1") (pintype "passive"))
      (node (ref "U10") (pin "3") (pinfunction "Q3_3") (pintype "output"))
    )
    (net (code "41") (name "/CH19_IN") (class "Default")
      (node (ref "C22") (pin "2") (pinfunction "2_2") (pintype "passive"))
      (node (ref "R16") (pin "2") (pinfunction "2_2") (pintype "passive"))
      (node (ref "U24") (pin "3") (pinfunction "OUT_3") (pintype "passive"))
      (node (ref "U27") (pin "5") (pinfunction "CH4_5") (pintype "input"))
    )
    (net (code "42") (name "/CH20") (class "Default")
      (node (ref "Q6") (pin "1") (pinfunction "G_1") (pintype "passive"))
      (node (ref "U10") (pin "4") (pinfunction "Q4_4") (pintype "output"))
    )
    (net (code "43") (name "/CH20_IN") (class "Default")
      (node (ref "C39") (pin "2") (pinfunction "2_2") (pintype "passive"))
      (node (ref "R33") (pin "2") (pinfunction "2_2") (pintype "passive"))
      (node (ref "U27") (pin "4") (pinfunction "CH3_4") (pintype "input"))
      (node (ref "U39") (pin "3") (pinfunction "OUT_3") (pintype "passive"))
    )
    (net (code "44") (name "/CH21") (class "Default")
      (node (ref "Q19") (pin "1") (pinfunction "G_1") (pintype "passive"))
      (node (ref "U10") (pin "5") (pinfunction "Q5_5") (pintype "output"))
    )
    (net (code "45") (name "/CH21_IN") (class "Default")
      (node (ref "C12") (pin "2") (pinfunction "2_2") (pintype "passive"))
      (node (ref "R6") (pin "2") (pinfunction "2_2") (pintype "passive"))
      (node (ref "U15") (pin "3") (pinfunction "OUT_3") (pintype "passive"))
      (node (ref "U27") (pin "3") (pinfunction "CH2_3") (pintype "input"))
    )
    (net (code "46") (name "/CH22") (class "Default")
      (node (ref "Q2") (pin "1") (pinfunction "G_1") (pintype "passive"))
      (node (ref "U10") (pin "6") (pinfunction "Q6_6") (pintype "output"))
    )
    (net (code "47") (name "/CH22_IN") (class "Default")
      (node (ref "C31") (pin "2") (pinfunction "2_2") (pintype "passive"))
      (node (ref "R27") (pin "2") (pinfunction "2_2") (pintype "passive"))
      (node (ref "U27") (pin "2") (pinfunction "CH1_2") (pintype "input"))
      (node (ref "U33") (pin "3") (pinfunction "OUT_3") (pintype "passive"))
    )
    (net (code "48") (name "/CH23") (class "Default")
      (node (ref "Q17") (pin "1") (pinfunction "G_1") (pintype "passive"))
      (node (ref "U10") (pin "7") (pinfunction "Q7_7") (pintype "output"))
    )
    (net (code "49") (name "/CH23_IN") (class "Default")
      (node (ref "C20") (pin "2") (pinfunction "2_2") (pintype "passive"))
      (node (ref "R14") (pin "2") (pinfunction "2_2") (pintype "passive"))
      (node (ref "U22") (pin "3") (pinfunction "OUT_3") (pintype "passive"))
      (node (ref "U27") (pin "1") (pinfunction "CH0_1") (pintype "input"))
    )
    (net (code "50") (name "/CLOCK") (class "Default")
      (node (ref "MD1") (pin "3") (pinfunction "LRCLK2_3") (pintype "passive"))
      (node (ref "U10") (pin "11") (pinfunction "SHCP_11") (pintype "input"))
      (node (ref "U7") (pin "11") (pinfunction "SHCP_11") (pintype "input"))
      (node (ref "U8") (pin "11") (pinfunction "SHCP_11") (pintype "input"))
    )
    (net (code "51") (name "/CS1") (class "Default")
      (node (ref "MD1") (pin "5") (pinfunction "IN2_5") (pintype "passive"))
      (node (ref "R9") (pin "1") (pinfunction "1_1") (pintype "passive"))
      (node (ref "U18") (pin "10") (pinfunction "~{CS}/SHDN_10") (pintype "input"))
    )
    (net (code "52") (name "/CS2") (class "Default")
      (node (ref "MD1") (pin "6") (pinfunction "OUT1D_6") (pintype "passive"))
      (node (ref "R20") (pin "1") (pinfunction "1_1") (pintype "passive"))
      (node (ref "U26") (pin "10") (pinfunction "~{CS}/SHDN_10") (pintype "input"))
    )
    (net (code "53") (name "/CS3") (class "Default")
      (node (ref "MD1") (pin "7") (pinfunction "RX2_7") (pintype "passive"))
      (node (ref "R21") (pin "1") (pinfunction "1_1") (pintype "passive"))
      (node (ref "U27") (pin "10") (pinfunction "~{CS}/SHDN_10") (pintype "input"))
    )
    (net (code "54") (name "/LATCH") (class "Default")
      (node (ref "MD1") (pin "4") (pinfunction "BCLK2_4") (pintype "passive"))
      (node (ref "U10") (pin "12") (pinfunction "STCP_12") (pintype "input"))
      (node (ref "U7") (pin "12") (pinfunction "STCP_12") (pintype "input"))
      (node (ref "U8") (pin "12") (pinfunction "STCP_12") (pintype "input"))
    )
    (net (code "55") (name "/MISO") (class "Default")
      (node (ref "MD1") (pin "12") (pinfunction "MISO_12") (pintype "passive"))
      (node (ref "U18") (pin "12") (pinfunction "DOUT_12") (pintype "tri_state"))
      (node (ref "U26") (pin "12") (pinfunction "DOUT_12") (pintype "tri_state"))
      (node (ref "U27") (pin "12") (pinfunction "DOUT_12") (pintype "tri_state"))
    )
    (net (code "56") (name "/MOSI") (class "Default")
      (node (ref "MD1") (pin "11") (pinfunction "MOSI_11") (pintype "passive"))
      (node (ref "U18") (pin "11") (pinfunction "DIN_11") (pintype "input"))
      (node (ref "U26") (pin "11") (pinfunction "DIN_11") (pintype "input"))
      (node (ref "U27") (pin "11") (pinfunction "DIN_11") (pintype "input"))
    )
    (net (code "57") (name "/SCK") (class "Default")
      (node (ref "MD1") (pin "13") (pinfunction "SCLK_13") (pintype "passive"))
      (node (ref "U18") (pin "13") (pinfunction "CLK_13") (pintype "input"))
      (node (ref "U26") (pin "13") (pinfunction "CLK_13") (pintype "input"))
      (node (ref "U27") (pin "13") (pinfunction "CLK_13") (pintype "input"))
    )
    (net (code "58") (name "/SER1") (class "Default")
      (node (ref "MD1") (pin "2") (pinfunction "OUT2_2") (pintype "passive"))
      (node (ref "U7") (pin "14") (pinfunction "DS_14") (pintype "input"))
    )
    (net (code "59") (name "5V") (class "Default")
      (node (ref "C16") (pin "1") (pintype "passive"))
      (node (ref "U1") (pin "5") (pinfunction "EN/SYNC_5") (pintype "input"))
      (node (ref "U1") (pin "7") (pinfunction "VIN_7") (pintype "passive"))
    )
    (net (code "60") (name "AGND") (class "Default")
      (node (ref "C32") (pin "2") (pinfunction "2_2") (pintype "passive"))
      (node (ref "C33") (pin "2") (pinfunction "-_2") (pintype "passive"))
      (node (ref "IC1") (pin "2") (pinfunction "GND_1_2") (pintype "passive"))
      (node (ref "IC1") (pin "4") (pinfunction "GND_2_4") (pintype "passive"))
      (node (ref "NT1") (pin "2") (pinfunction "2_2") (pintype "passive"))
      (node (ref "U18") (pin "14") (pinfunction "AGND_14") (pintype "power_in"))
      (node (ref "U26") (pin "14") (pinfunction "AGND_14") (pintype "power_in"))
      (node (ref "U27") (pin "14") (pinfunction "AGND_14") (pintype "power_in"))
    )
    (net (code "61") (name "AVCC_3V3") (class "Default")
      (node (ref "C33") (pin "1") (pinfunction "+_1") (pintype "passive"))
      (node (ref "IC1") (pin "3") (pinfunction "OUT_3") (pintype "passive"))
      (node (ref "Q1") (pin "2") (pinfunction "S_2") (pintype "passive"))
      (node (ref "Q10") (pin "2") (pinfunction "S_2") (pintype "passive"))
      (node (ref "Q11") (pin "2") (pinfunction "S_2") (pintype "passive"))
      (node (ref "Q12") (pin "2") (pinfunction "S_2") (pintype "passive"))
      (node (ref "Q13") (pin "2") (pinfunction "S_2") (pintype "passive"))
      (node (ref "Q14") (pin "2") (pinfunction "S_2") (pintype "passive"))
      (node (ref "Q15") (pin "2") (pinfunction "S_2") (pintype "passive"))
      (node (ref "Q16") (pin "2") (pinfunction "S_2") (pintype "passive"))
      (node (ref "Q17") (pin "2") (pinfunction "S_2") (pintype "passive"))
      (node (ref "Q18") (pin "2") (pinfunction "S_2") (pintype "passive"))
      (node (ref "Q19") (pin "2") (pinfunction "S_2") (pintype "passive"))
      (node (ref "Q2") (pin "2") (pinfunction "S_2") (pintype "passive"))
      (node (ref "Q20") (pin "2") (pinfunction "S_2") (pintype "passive"))
      (node (ref "Q21") (pin "2") (pinfunction "S_2") (pintype "passive"))
      (node (ref "Q22") (pin "2") (pinfunction "S_2") (pintype "passive"))
      (node (ref "Q23") (pin "2") (pinfunction "S_2") (pintype "passive"))
      (node (ref "Q24") (pin "2") (pinfunction "S_2") (pintype "passive"))
      (node (ref "Q3") (pin "2") (pinfunction "S_2") (pintype "passive"))
      (node (ref "Q4") (pin "2") (pinfunction "S_2") (pintype "passive"))
      (node (ref "Q5") (pin "2") (pinfunction "S_2") (pintype "passive"))
      (node (ref "Q6") (pin "2") (pinfunction "S_2") (pintype "passive"))
      (node (ref "Q7") (pin "2") (pinfunction "S_2") (pintype "passive"))
      (node (ref "Q8") (pin "2") (pinfunction "S_2") (pintype "passive"))
      (node (ref "Q9") (pin "2") (pinfunction "S_2") (pintype "passive"))
      (node (ref "U18") (pin "15") (pinfunction "VREF_15") (pintype "input"))
      (node (ref "U26") (pin "15") (pinfunction "VREF_15") (pintype "input"))
      (node (ref "U27") (pin "15") (pinfunction "VREF_15") (pintype "input"))
    )
    (net (code "62") (name "GND") (class "Default")
      (node (ref "C1") (pin "2") (pintype "passive"))
      (node (ref "C16") (pin "2") (pintype "passive"))
      (node (ref "C2") (pin "2") (pintype "passive"))
      (node (ref "C24") (pin "2") (pintype "passive"))
      (node (ref "C25") (pin "2") (pintype "passive"))
      (node (ref "C40") (pin "1") (pintype "passive"))
      (node (ref "C5") (pin "2") (pintype "passive"))
      (node (ref "C8") (pin "1") (pinfunction "1_1") (pintype "passive"))
      (node (ref "D1") (pin "1") (pinfunction "A_1") (pintype "passive"))
      (node (ref "J2") (pin "N") (pinfunction "NEG_N") (pintype "passive"))
      (node (ref "MD1") (pin "43") (pinfunction "GND_43") (pintype "passive"))
      (node (ref "MD1") (pin "45") (pinfunction "GND_45") (pintype "passive"))
      (node (ref "MD1") (pin "46") (pinfunction "GND_46") (pintype "passive"))
      (node (ref "NT1") (pin "1") (pinfunction "1_1") (pintype "passive"))
      (node (ref "R18") (pin "1") (pinfunction "1_1") (pintype "passive"))
      (node (ref "R19") (pin "1") (pinfunction "1_1") (pintype "passive"))
      (node (ref "U1") (pin "6") (pinfunction "AGND_6") (pintype "power_in"))
      (node (ref "U1") (pin "8") (pinfunction "PGND_8") (pintype "power_in"))
      (node (ref "U1") (pin "9") (pinfunction "PAD_9") (pintype "power_in"))
      (node (ref "U10") (pin "13") (pinfunction "~{OE}_13") (pintype "input"))
      (node (ref "U10") (pin "8") (pinfunction "GND_8") (pintype "power_in"))
      (node (ref "U11") (pin "4") (pinfunction "V+_4") (pintype "power_in"))
      (node (ref "U12") (pin "5") (pinfunction "V-_5") (pintype "power_in"))
      (node (ref "U13") (pin "5") (pinfunction "V-_5") (pintype "power_in"))
      (node (ref "U14") (pin "5") (pinfunction "V-_5") (pintype "power_in"))
      (node (ref "U15") (pin "5") (pinfunction "V-_5") (pintype "power_in"))
      (node (ref "U16") (pin "5") (pinfunction "V-_5") (pintype "power_in"))
      (node (ref "U17") (pin "5") (pinfunction "V-_5") (pintype "power_in"))
      (node (ref "U18") (pin "9") (pinfunction "DGND_9") (pintype "power_in"))
      (node (ref "U19") (pin "5") (pinfunction "V-_5") (pintype "power_in"))
      (node (ref "U20") (pin "5") (pinfunction "V-_5") (pintype "power_in"))
      (node (ref "U21") (pin "5") (pinfunction "V-_5") (pintype "power_in"))
      (node (ref "U22") (pin "5") (pinfunction "V-_5") (pintype "power_in"))
      (node (ref "U23") (pin "5") (pinfunction "V-_5") (pintype "power_in"))
      (node (ref "U24") (pin "5") (pinfunction "V-_5") (pintype "power_in"))
      (node (ref "U26") (pin "9") (pinfunction "DGND_9") (pintype "power_in"))
      (node (ref "U27") (pin "9") (pinfunction "DGND_9") (pintype "power_in"))
      (node (ref "U28") (pin "5") (pinfunction "V-_5") (pintype "power_in"))
      (node (ref "U29") (pin "5") (pinfunction "V-_5") (pintype "power_in"))
      (node (ref "U30") (pin "5") (pinfunction "V-_5") (pintype "power_in"))
      (node (ref "U31") (pin "5") (pinfunction "V-_5") (pintype "power_in"))
      (node (ref "U32") (pin "5") (pinfunction "V-_5") (pintype "power_in"))
      (node (ref "U33") (pin "5") (pinfunction "V-_5") (pintype "power_in"))
      (node (ref "U34") (pin "5") (pinfunction "V-_5") (pintype "power_in"))
      (node (ref "U35") (pin "5") (pinfunction "V-_5") (pintype "power_in"))
      (node (ref "U36") (pin "5") (pinfunction "V-_5") (pintype "power_in"))
      (node (ref "U37") (pin "5") (pinfunction "V-_5") (pintype "power_in"))
      (node (ref "U38") (pin "5") (pinfunction "V-_5") (pintype "power_in"))
      (node (ref "U39") (pin "5") (pinfunction "V-_5") (pintype "power_in"))
      (node (ref "U7") (pin "13") (pinfunction "~{OE}_13") (pintype "input"))
      (node (ref "U7") (pin "8") (pinfunction "GND_8") (pintype "power_in"))
      (node (ref "U8") (pin "13") (pinfunction "~{OE}_13") (pintype "input"))
      (node (ref "U8") (pin "8") (pinfunction "GND_8") (pintype "power_in"))
      (node (ref "U9") (pin "6") (pinfunction "AGND_6") (pintype "power_in"))
      (node (ref "U9") (pin "8") (pinfunction "PGND_8") (pintype "power_in"))
      (node (ref "U9") (pin "9") (pinfunction "PAD_9") (pintype "power_in"))
    )
    (net (code "63") (name "Net-(D1-A-Pad2)") (class "Default")
      (node (ref "D1") (pin "2") (pinfunction "A_2") (pintype "passive"))
      (node (ref "D2") (pin "1") (pinfunction "1_1") (pintype "passive"))
      (node (ref "F1") (pin "2") (pinfunction "2_2") (pintype "passive"))
    )
    (net (code "64") (name "Net-(MD1-VIN)") (class "Default")
      (node (ref "J34") (pin "2") (pinfunction "2_2") (pintype "passive"))
      (node (ref "MD1") (pin "42") (pinfunction "VIN_42") (pintype "passive"))
    )
    (net (code "65") (name "Net-(Q1-D)") (class "Default")
      (node (ref "J1") (pin "1") (pinfunction "1_1") (pintype "passive"))
      (node (ref "Q1") (pin "3") (pinfunction "D_3") (pintype "passive"))
    )
    (net (code "66") (name "Net-(Q2-D)") (class "Default")
      (node (ref "J1") (pin "23") (pinfunction "23_23") (pintype "passive"))
      (node (ref "Q2") (pin "3") (pinfunction "D_3") (pintype "passive"))
    )
    (net (code "67") (name "Net-(Q3-D)") (class "Default")
      (node (ref "J1") (pin "5") (pinfunction "5_5") (pintype "passive"))
      (node (ref "Q3") (pin "3") (pinfunction "D_3") (pintype "passive"))
    )
    (net (code "68") (name "Net-(Q4-D)") (class "Default")
      (node (ref "J1") (pin "9") (pinfunction "9_9") (pintype "passive"))
      (node (ref "Q4") (pin "3") (pinfunction "D_3") (pintype "passive"))
    )
    (net (code "69") (name "Net-(Q5-D)") (class "Default")
      (node (ref "J1") (pin "13") (pinfunction "13_13") (pintype "passive"))
      (node (ref "Q5") (pin "3") (pinfunction "D_3") (pintype "passive"))
    )
    (net (code "70") (name "Net-(Q6-D)") (class "Default")
      (node (ref "J1") (pin "21") (pinfunction "21_21") (pintype "passive"))
      (node (ref "Q6") (pin "3") (pinfunction "D_3") (pintype "passive"))
    )
    (net (code "71") (name "Net-(Q7-D)") (class "Default")
      (node (ref "J1") (pin "17") (pinfunction "17_17") (pintype "passive"))
      (node (ref "Q7") (pin "3") (pinfunction "D_3") (pintype "passive"))
    )
    (net (code "72") (name "Net-(Q8-D)") (class "Default")
      (node (ref "J1") (pin "7") (pinfunction "7_7") (pintype "passive"))
      (node (ref "Q8") (pin "3") (pinfunction "D_3") (pintype "passive"))
    )
    (net (code "73") (name "Net-(Q9-D)") (class "Default")
      (node (ref "J1") (pin "19") (pinfunction "19_19") (pintype "passive"))
      (node (ref "Q9") (pin "3") (pinfunction "D_3") (pintype "passive"))
    )
    (net (code "74") (name "Net-(Q10-D)") (class "Default")
      (node (ref "J1") (pin "3") (pinfunction "3_3") (pintype "passive"))
      (node (ref "Q10") (pin "3") (pinfunction "D_3") (pintype "passive"))
    )
    (net (code "75") (name "Net-(Q11-D)") (class "Default")
      (node (ref "J1") (pin "11") (pinfunction "11_11") (pintype "passive"))
      (node (ref "Q11") (pin "3") (pinfunction "D_3") (pintype "passive"))
    )
    (net (code "76") (name "Net-(Q12-D)") (class "Default")
      (node (ref "J1") (pin "15") (pinfunction "15_15") (pintype "passive"))
      (node (ref "Q12") (pin "3") (pinfunction "D_3") (pintype "passive"))
    )
    (net (code "77") (name "Net-(Q13-D)") (class "Default")
      (node (ref "J1") (pin "4") (pinfunction "4_4") (pintype "passive"))
      (node (ref "Q13") (pin "3") (pinfunction "D_3") (pintype "passive"))
    )
    (net (code "78") (name "Net-(Q14-D)") (class "Default")
      (node (ref "J1") (pin "8") (pinfunction "8_8") (pintype "passive"))
      (node (ref "Q14") (pin "3") (pinfunction "D_3") (pintype "passive"))
    )
    (net (code "79") (name "Net-(Q15-D)") (class "Default")
      (node (ref "J1") (pin "12") (pinfunction "12_12") (pintype "passive"))
      (node (ref "Q15") (pin "3") (pinfunction "D_3") (pintype "passive"))
    )
    (net (code "80") (name "Net-(Q16-D)") (class "Default")
      (node (ref "J1") (pin "16") (pinfunction "16_16") (pintype "passive"))
      (node (ref "Q16") (pin "3") (pinfunction "D_3") (pintype "passive"))
    )
    (net (code "81") (name "Net-(Q17-D)") (class "Default")
      (node (ref "J1") (pin "24") (pinfunction "24_24") (pintype "passive"))
      (node (ref "Q17") (pin "3") (pinfunction "D_3") (pintype "passive"))
    )
    (net (code "82") (name "Net-(Q18-D)") (class "Default")
      (node (ref "J1") (pin "20") (pinfunction "20_20") (pintype "passive"))
      (node (ref "Q18") (pin "3") (pinfunction "D_3") (pintype "passive"))
    )
    (net (code "83") (name "Net-(Q19-D)") (class "Default")
      (node (ref "J1") (pin "22") (pinfunction "22_22") (pintype "passive"))
      (node (ref "Q19") (pin "3") (pinfunction "D_3") (pintype "passive"))
    )
    (net (code "84") (name "Net-(Q20-D)") (class "Default")
      (node (ref "J1") (pin "18") (pinfunction "18_18") (pintype "passive"))
      (node (ref "Q20") (pin "3") (pinfunction "D_3") (pintype "passive"))
    )
    (net (code "85") (name "Net-(Q21-D)") (class "Default")
      (node (ref "J1") (pin "2") (pinfunction "2_2") (pintype "passive"))
      (node (ref "Q21") (pin "3") (pinfunction "D_3") (pintype "passive"))
    )
    (net (code "86") (name "Net-(Q22-D)") (class "Default")
      (node (ref "J1") (pin "6") (pinfunction "6_6") (pintype "passive"))
      (node (ref "Q22") (pin "3") (pinfunction "D_3") (pintype "passive"))
    )
    (net (code "87") (name "Net-(Q23-D)") (class "Default")
      (node (ref "J1") (pin "10") (pinfunction "10_10") (pintype "passive"))
      (node (ref "Q23") (pin "3") (pinfunction "D_3") (pintype "passive"))
    )
    (net (code "88") (name "Net-(Q24-D)") (class "Default")
      (node (ref "J1") (pin "14") (pinfunction "14_14") (pintype "passive"))
      (node (ref "Q24") (pin "3") (pinfunction "D_3") (pintype "passive"))
    )
    (net (code "89") (name "Net-(U1-BOOT)") (class "Default")
      (node (ref "C15") (pin "1") (pintype "passive"))
      (node (ref "U1") (pin "2") (pinfunction "BOOT_2") (pintype "passive"))
    )
    (net (code "90") (name "Net-(U1-FB)") (class "Default")
      (node (ref "C23") (pin "2") (pintype "passive"))
      (node (ref "R11") (pin "1") (pinfunction "1_1") (pintype "passive"))
      (node (ref "R19") (pin "2") (pinfunction "2_2") (pintype "passive"))
      (node (ref "U1") (pin "4") (pinfunction "FB_4") (pintype "input"))
    )
    (net (code "91") (name "Net-(U1-SW)") (class "Default")
      (node (ref "C15") (pin "2") (pintype "passive"))
      (node (ref "L2") (pin "1") (pinfunction "1_1") (pintype "passive"))
      (node (ref "U1") (pin "1") (pinfunction "SW_1") (pintype "passive"))
    )
    (net (code "92") (name "Net-(U1-VCC)") (class "Default")
      (node (ref "C40") (pin "2") (pintype "passive"))
      (node (ref "U1") (pin "3") (pinfunction "VCC_3") (pintype "power_in"))
    )
    (net (code "93") (name "Net-(U7-Q7S)") (class "Default")
      (node (ref "U7") (pin "9") (pinfunction "Q7S_9") (pintype "output"))
      (node (ref "U8") (pin "14") (pinfunction "DS_14") (pintype "input"))
    )
    (net (code "94") (name "Net-(U8-VCC)") (class "Default")
      (node (ref "C6") (pin "1") (pinfunction "1_1") (pintype "passive"))
      (node (ref "U8") (pin "10") (pinfunction "~{MR}_10") (pintype "input"))
      (node (ref "U8") (pin "16") (pinfunction "VCC_16") (pintype "power_in"))
    )
    (net (code "95") (name "Net-(U9-BOOT)") (class "Default")
      (node (ref "C3") (pin "1") (pintype "passive"))
      (node (ref "U9") (pin "2") (pinfunction "BOOT_2") (pintype "passive"))
    )
    (net (code "96") (name "Net-(U9-FB)") (class "Default")
      (node (ref "C4") (pin "2") (pintype "passive"))
      (node (ref "R17") (pin "1") (pinfunction "1_1") (pintype "passive"))
      (node (ref "R18") (pin "2") (pinfunction "2_2") (pintype "passive"))
      (node (ref "U9") (pin "4") (pinfunction "FB_4") (pintype "input"))
    )
    (net (code "97") (name "Net-(U9-SW)") (class "Default")
      (node (ref "C3") (pin "2") (pintype "passive"))
      (node (ref "L1") (pin "1") (pinfunction "1_1") (pintype "passive"))
      (node (ref "U9") (pin "1") (pinfunction "SW_1") (pintype "passive"))
    )
    (net (code "98") (name "Net-(U9-VCC)") (class "Default")
      (node (ref "C2") (pin "1") (pintype "passive"))
      (node (ref "U9") (pin "3") (pinfunction "VCC_3") (pintype "power_in"))
    )
    (net (code "99") (name "Net-(U10-DS)") (class "Default")
      (node (ref "U10") (pin "14") (pinfunction "DS_14") (pintype "input"))
      (node (ref "U8") (pin "9") (pinfunction "Q7S_9") (pintype "output"))
    )
    (net (code "100") (name "Net-(U10-VCC)") (class "Default")
      (node (ref "C7") (pin "1") (pinfunction "1_1") (pintype "passive"))
      (node (ref "U10") (pin "10") (pinfunction "~{MR}_10") (pintype "input"))
      (node (ref "U10") (pin "16") (pinfunction "VCC_16") (pintype "power_in"))
    )
    (net (code "101") (name "Net-(U11-IN+)") (class "Default")
      (node (ref "R1") (pin "1") (pinfunction "1_1") (pintype "passive"))
      (node (ref "R2") (pin "2") (pinfunction "2_2") (pintype "passive"))
      (node (ref "U11") (pin "2") (pinfunction "IN+_2") (pintype "passive"))
    )
    (net (code "102") (name "Net-(U11-IN-)") (class "Default")
      (node (ref "U11") (pin "1") (pinfunction "IN-_1") (pintype "passive"))
      (node (ref "U11") (pin "3") (pinfunction "OUT_3") (pintype "passive"))
    )
    (net (code "103") (name "Net-(U12-IN-)") (class "Default")
      (node (ref "C9") (pin "1") (pinfunction "1_1") (pintype "passive"))
      (node (ref "J3") (pin "2") (pinfunction "2_2") (pintype "passive"))
      (node (ref "R3") (pin "1") (pinfunction "1_1") (pintype "passive"))
      (node (ref "U12") (pin "1") (pinfunction "IN-_1") (pintype "passive"))
    )
    (net (code "104") (name "Net-(U13-IN-)") (class "Default")
      (node (ref "C10") (pin "1") (pinfunction "1_1") (pintype "passive"))
      (node (ref "J3") (pin "6") (pinfunction "6_6") (pintype "passive"))
      (node (ref "R4") (pin "1") (pinfunction "1_1") (pintype "passive"))
      (node (ref "U13") (pin "1") (pinfunction "IN-_1") (pintype "passive"))
    )
    (net (code "105") (name "Net-(U14-IN-)") (class "Default")
      (node (ref "C11") (pin "1") (pinfunction "1_1") (pintype "passive"))
      (node (ref "J3") (pin "10") (pinfunction "10_10") (pintype "passive"))
      (node (ref "R5") (pin "1") (pinfunction "1_1") (pintype "passive"))
      (node (ref "U14") (pin "1") (pinfunction "IN-_1") (pintype "passive"))
    )
    (net (code "106") (name "Net-(U15-IN-)") (class "Default")
      (node (ref "C12") (pin "1") (pinfunction "1_1") (pintype "passive"))
      (node (ref "J3") (pin "22") (pinfunction "22_22") (pintype "passive"))
      (node (ref "R6") (pin "1") (pinfunction "1_1") (pintype "passive"))
      (node (ref "U15") (pin "1") (pinfunction "IN-_1") (pintype "passive"))
    )
    (net (code "107") (name "Net-(U16-IN-)") (class "Default")
      (node (ref "C13") (pin "1") (pinfunction "1_1") (pintype "passive"))
      (node (ref "J3") (pin "14") (pinfunction "14_14") (pintype "passive"))
      (node (ref "R7") (pin "1") (pinfunction "1_1") (pintype "passive"))
      (node (ref "U16") (pin "1") (pinfunction "IN-_1") (pintype "passive"))
    )
    (net (code "108") (name "Net-(U17-IN-)") (class "Default")
      (node (ref "C14") (pin "1") (pinfunction "1_1") (pintype "passive"))
      (node (ref "J3") (pin "18") (pinfunction "18_18") (pintype "passive"))
      (node (ref "R8") (pin "1") (pinfunction "1_1") (pintype "passive"))
      (node (ref "U17") (pin "1") (pinfunction "IN-_1") (pintype "passive"))
    )
    (net (code "109") (name "Net-(U19-IN-)") (class "Default")
      (node (ref "C17") (pin "1") (pinfunction "1_1") (pintype "passive"))
      (node (ref "J3") (pin "4") (pinfunction "4_4") (pintype "passive"))
      (node (ref "R10") (pin "1") (pinfunction "1_1") (pintype "passive"))
      (node (ref "U19") (pin "1") (pinfunction "IN-_1") (pintype "passive"))
    )
    (net (code "110") (name "Net-(U20-IN-)") (class "Default")
      (node (ref "C18") (pin "1") (pinfunction "1_1") (pintype "passive"))
      (node (ref "J3") (pin "8") (pinfunction "8_8") (pintype "passive"))
      (node (ref "R12") (pin "1") (pinfunction "1_1") (pintype "passive"))
      (node (ref "U20") (pin "1") (pinfunction "IN-_1") (pintype "passive"))
    )
    (net (code "111") (name "Net-(U21-IN-)") (class "Default")
      (node (ref "C19") (pin "1") (pinfunction "1_1") (pintype "passive"))
      (node (ref "J3") (pin "12") (pinfunction "12_12") (pintype "passive"))
      (node (ref "R13") (pin "1") (pinfunction "1_1") (pintype "passive"))
      (node (ref "U21") (pin "1") (pinfunction "IN-_1") (pintype "passive"))
    )
    (net (code "112") (name "Net-(U22-IN-)") (class "Default")
      (node (ref "C20") (pin "1") (pinfunction "1_1") (pintype "passive"))
      (node (ref "J3") (pin "24") (pinfunction "24_24") (pintype "passive"))
      (node (ref "R14") (pin "1") (pinfunction "1_1") (pintype "passive"))
      (node (ref "U22") (pin "1") (pinfunction "IN-_1") (pintype "passive"))
    )
    (net (code "113") (name "Net-(U23-IN-)") (class "Default")
      (node (ref "C21") (pin "1") (pinfunction "1_1") (pintype "passive"))
      (node (ref "J3") (pin "16") (pinfunction "16_16") (pintype "passive"))
      (node (ref "R15") (pin "1") (pinfunction "1_1") (pintype "passive"))
      (node (ref "U23") (pin "1") (pinfunction "IN-_1") (pintype "passive"))
    )
    (net (code "114") (name "Net-(U24-IN-)") (class "Default")
      (node (ref "C22") (pin "1") (pinfunction "1_1") (pintype "passive"))
      (node (ref "J3") (pin "20") (pinfunction "20_20") (pintype "passive"))
      (node (ref "R16") (pin "1") (pinfunction "1_1") (pintype "passive"))
      (node (ref "U24") (pin "1") (pinfunction "IN-_1") (pintype "passive"))
    )
    (net (code "115") (name "Net-(U28-IN-)") (class "Default")
      (node (ref "C26") (pin "1") (pinfunction "1_1") (pintype "passive"))
      (node (ref "J3") (pin "3") (pinfunction "3_3") (pintype "passive"))
      (node (ref "R22") (pin "1") (pinfunction "1_1") (pintype "passive"))
      (node (ref "U28") (pin "1") (pinfunction "IN-_1") (pintype "passive"))
    )
    (net (code "116") (name "Net-(U29-IN-)") (class "Default")
      (node (ref "C27") (pin "1") (pinfunction "1_1") (pintype "passive"))
      (node (ref "J3") (pin "7") (pinfunction "7_7") (pintype "passive"))
      (node (ref "R23") (pin "1") (pinfunction "1_1") (pintype "passive"))
      (node (ref "U29") (pin "1") (pinfunction "IN-_1") (pintype "passive"))
    )
    (net (code "117") (name "Net-(U30-IN-)") (class "Default")
      (node (ref "C28") (pin "1") (pinfunction "1_1") (pintype "passive"))
      (node (ref "J3") (pin "11") (pinfunction "11_11") (pintype "passive"))
      (node (ref "R24") (pin "1") (pinfunction "1_1") (pintype "passive"))
      (node (ref "U30") (pin "1") (pinfunction "IN-_1") (pintype "passive"))
    )
    (net (code "118") (name "Net-(U31-IN-)") (class "Default")
      (node (ref "C29") (pin "1") (pinfunction "1_1") (pintype "passive"))
      (node (ref "J3") (pin "15") (pinfunction "15_15") (pintype "passive"))
      (node (ref "R25") (pin "1") (pinfunction "1_1") (pintype "passive"))
      (node (ref "U31") (pin "1") (pinfunction "IN-_1") (pintype "passive"))
    )
    (net (code "119") (name "Net-(U32-IN-)") (class "Default")
      (node (ref "C30") (pin "1") (pinfunction "1_1") (pintype "passive"))
      (node (ref "J3") (pin "19") (pinfunction "19_19") (pintype "passive"))
      (node (ref "R26") (pin "1") (pinfunction "1_1") (pintype "passive"))
      (node (ref "U32") (pin "1") (pinfunction "IN-_1") (pintype "passive"))
    )
    (net (code "120") (name "Net-(U33-IN-)") (class "Default")
      (node (ref "C31") (pin "1") (pinfunction "1_1") (pintype "passive"))
      (node (ref "J3") (pin "23") (pinfunction "23_23") (pintype "passive"))
      (node (ref "R27") (pin "1") (pinfunction "1_1") (pintype "passive"))
      (node (ref "U33") (pin "1") (pinfunction "IN-_1") (pintype "passive"))
    )
    (net (code "121") (name "Net-(U34-IN-)") (class "Default")
      (node (ref "C34") (pin "1") (pinfunction "1_1") (pintype "passive"))
      (node (ref "J3") (pin "1") (pinfunction "1_1") (pintype "passive"))
      (node (ref "R28") (pin "1") (pinfunction "1_1") (pintype "passive"))
      (node (ref "U34") (pin "1") (pinfunction "IN-_1") (pintype "passive"))
    )
    (net (code "122") (name "Net-(U35-IN-)") (class "Default")
      (node (ref "C35") (pin "1") (pinfunction "1_1") (pintype "passive"))
      (node (ref "J3") (pin "5") (pinfunction "5_5") (pintype "passive"))
      (node (ref "R29") (pin "1") (pinfunction "1_1") (pintype "passive"))
      (node (ref "U35") (pin "1") (pinfunction "IN-_1") (pintype "passive"))
    )
    (net (code "123") (name "Net-(U36-IN-)") (class "Default")
      (node (ref "C36") (pin "1") (pinfunction "1_1") (pintype "passive"))
      (node (ref "J3") (pin "9") (pinfunction "9_9") (pintype "passive"))
      (node (ref "R30") (pin "1") (pinfunction "1_1") (pintype "passive"))
      (node (ref "U36") (pin "1") (pinfunction "IN-_1") (pintype "passive"))
    )
    (net (code "124") (name "Net-(U37-IN-)") (class "Default")
      (node (ref "C37") (pin "1") (pinfunction "1_1") (pintype "passive"))
      (node (ref "J3") (pin "13") (pinfunction "13_13") (pintype "passive"))
      (node (ref "R31") (pin "1") (pinfunction "1_1") (pintype "passive"))
      (node (ref "U37") (pin "1") (pinfunction "IN-_1") (pintype "passive"))
    )
    (net (code "125") (name "Net-(U38-IN-)") (class "Default")
      (node (ref "C38") (pin "1") (pinfunction "1_1") (pintype "passive"))
      (node (ref "J3") (pin "17") (pinfunction "17_17") (pintype "passive"))
      (node (ref "R32") (pin "1") (pinfunction "1_1") (pintype "passive"))
      (node (ref "U38") (pin "1") (pinfunction "IN-_1") (pintype "passive"))
    )
    (net (code "126") (name "Net-(U39-IN-)") (class "Default")
      (node (ref "C39") (pin "1") (pinfunction "1_1") (pintype "passive"))
      (node (ref "J3") (pin "21") (pinfunction "21_21") (pintype "passive"))
      (node (ref "R33") (pin "1") (pinfunction "1_1") (pintype "passive"))
      (node (ref "U39") (pin "1") (pinfunction "IN-_1") (pintype "passive"))
    )
    (net (code "127") (name "VBAT_RAW") (class "Default")
      (node (ref "F1") (pin "1") (pinfunction "1_1") (pintype "passive"))
      (node (ref "J2") (pin "P") (pinfunction "POS_P") (pintype "passive"))
    )
    (net (code "128") (name "VCC_3V3") (class "Default")
      (node (ref "C23") (pin "1") (pintype "passive"))
      (node (ref "C24") (pin "1") (pintype "passive"))
      (node (ref "C25") (pin "1") (pintype "passive"))
      (node (ref "C6") (pin "2") (pinfunction "2_2") (pintype "passive"))
      (node (ref "C7") (pin "2") (pinfunction "2_2") (pintype "passive"))
      (node (ref "C8") (pin "2") (pinfunction "2_2") (pintype "passive"))
      (node (ref "L2") (pin "2") (pinfunction "2_2") (pintype "passive"))
      (node (ref "R11") (pin "2") (pinfunction "2_2") (pintype "passive"))
      (node (ref "R20") (pin "2") (pinfunction "2_2") (pintype "passive"))
      (node (ref "R21") (pin "2") (pinfunction "2_2") (pintype "passive"))
      (node (ref "R9") (pin "2") (pinfunction "2_2") (pintype "passive"))
      (node (ref "U11") (pin "5") (pinfunction "V-_5") (pintype "power_in"))
      (node (ref "U12") (pin "4") (pinfunction "V+_4") (pintype "power_in"))
      (node (ref "U13") (pin "4") (pinfunction "V+_4") (pintype "power_in"))
      (node (ref "U14") (pin "4") (pinfunction "V+_4") (pintype "power_in"))
      (node (ref "U15") (pin "4") (pinfunction "V+_4") (pintype "power_in"))
      (node (ref "U16") (pin "4") (pinfunction "V+_4") (pintype "power_in"))
      (node (ref "U17") (pin "4") (pinfunction "V+_4") (pintype "power_in"))
      (node (ref "U18") (pin "16") (pinfunction "VDD_16") (pintype "power_in"))
      (node (ref "U19") (pin "4") (pinfunction "V+_4") (pintype "power_in"))
      (node (ref "U20") (pin "4") (pinfunction "V+_4") (pintype "power_in"))
      (node (ref "U21") (pin "4") (pinfunction "V+_4") (pintype "power_in"))
      (node (ref "U22") (pin "4") (pinfunction "V+_4") (pintype "power_in"))
      (node (ref "U23") (pin "4") (pinfunction "V+_4") (pintype "power_in"))
      (node (ref "U24") (pin "4") (pinfunction "V+_4") (pintype "power_in"))
      (node (ref "U26") (pin "16") (pinfunction "VDD_16") (pintype "power_in"))
      (node (ref "U27") (pin "16") (pinfunction "VDD_16") (pintype "power_in"))
      (node (ref "U28") (pin "4") (pinfunction "V+_4") (pintype "power_in"))
      (node (ref "U29") (pin "4") (pinfunction "V+_4") (pintype "power_in"))
      (node (ref "U30") (pin "4") (pinfunction "V+_4") (pintype "power_in"))
      (node (ref "U31") (pin "4") (pinfunction "V+_4") (pintype "power_in"))
      (node (ref "U32") (pin "4") (pinfunction "V+_4") (pintype "power_in"))
      (node (ref "U33") (pin "4") (pinfunction "V+_4") (pintype "power_in"))
      (node (ref "U34") (pin "4") (pinfunction "V+_4") (pintype "power_in"))
      (node (ref "U35") (pin "4") (pinfunction "V+_4") (pintype "power_in"))
      (node (ref "U36") (pin "4") (pinfunction "V+_4") (pintype "power_in"))
      (node (ref "U37") (pin "4") (pinfunction "V+_4") (pintype "power_in"))
      (node (ref "U38") (pin "4") (pinfunction "V+_4") (pintype "power_in"))
      (node (ref "U39") (pin "4") (pinfunction "V+_4") (pintype "power_in"))
      (node (ref "U7") (pin "10") (pinfunction "~{MR}_10") (pintype "input"))
      (node (ref "U7") (pin "16") (pinfunction "VCC_16") (pintype "power_in"))
    )
    (net (code "129") (name "VCC_5V") (class "Default")
      (node (ref "C32") (pin "1") (pinfunction "1_1") (pintype "passive"))
      (node (ref "C4") (pin "1") (pintype "passive"))
      (node (ref "C5") (pin "1") (pintype "passive"))
      (node (ref "IC1") (pin "1") (pinfunction "IN_1") (pintype "passive"))
      (node (ref "J34") (pin "1") (pinfunction "1_1") (pintype "passive"))
      (node (ref "L1") (pin "2") (pinfunction "2_2") (pintype "passive"))
      (node (ref "R17") (pin "2") (pinfunction "2_2") (pintype "passive"))
    )
    (net (code "130") (name "VCC_12V") (class "Default")
      (node (ref "C1") (pin "1") (pintype "passive"))
      (node (ref "D2") (pin "2") (pinfunction "2_2") (pintype "passive"))
      (node (ref "U9") (pin "5") (pinfunction "EN/SYNC_5") (pintype "input"))
      (node (ref "U9") (pin "7") (pinfunction "VIN_7") (pintype "passive"))
    )
    (net (code "131") (name "unconnected-(MD1-3.3V-Pad44)") (class "Default")
      (node (ref "MD1") (pin "44") (pinfunction "3.3V_44") (pintype "passive+no_connect"))
    )
    (net (code "132") (name "unconnected-(MD1-3.3V-Pad47)") (class "Default")
      (node (ref "MD1") (pin "47") (pinfunction "3.3V_47") (pintype "passive+no_connect"))
    )
    (net (code "133") (name "unconnected-(MD1-A16-Pad40)") (class "Default")
      (node (ref "MD1") (pin "40") (pinfunction "A16_40") (pintype "passive+no_connect"))
    )
    (net (code "134") (name "unconnected-(MD1-A17-Pad41)") (class "Default")
      (node (ref "MD1") (pin "41") (pinfunction "A17_41") (pintype "passive+no_connect"))
    )
    (net (code "135") (name "unconnected-(MD1-CRX1-Pad23)") (class "Default")
      (node (ref "MD1") (pin "23") (pinfunction "CRX1_23") (pintype "passive+no_connect"))
    )
    (net (code "136") (name "unconnected-(MD1-CRX3-Pad30)") (class "Default")
      (node (ref "MD1") (pin "30") (pinfunction "CRX3_30") (pintype "passive+no_connect"))
    )
    (net (code "137") (name "unconnected-(MD1-CS-Pad10)") (class "Default")
      (node (ref "MD1") (pin "10") (pinfunction "CS_10") (pintype "passive+no_connect"))
    )
    (net (code "138") (name "unconnected-(MD1-CS-Pad36)") (class "Default")
      (node (ref "MD1") (pin "36") (pinfunction "CS_36") (pintype "passive+no_connect"))
    )
    (net (code "139") (name "unconnected-(MD1-CS-Pad37)") (class "Default")
      (node (ref "MD1") (pin "37") (pinfunction "CS_37") (pintype "passive+no_connect"))
    )
    (net (code "140") (name "unconnected-(MD1-CS1-Pad38)") (class "Default")
      (node (ref "MD1") (pin "38") (pinfunction "CS1_38") (pintype "passive+no_connect"))
    )
    (net (code "141") (name "unconnected-(MD1-CTX1-Pad22)") (class "Default")
      (node (ref "MD1") (pin "22") (pinfunction "CTX1_22") (pintype "passive+no_connect"))
    )
    (net (code "142") (name "unconnected-(MD1-CTX3-Pad31)") (class "Default")
      (node (ref "MD1") (pin "31") (pinfunction "CTX3_31") (pintype "passive+no_connect"))
    )
    (net (code "143") (name "unconnected-(MD1-MCLK2-Pad33)") (class "Default")
      (node (ref "MD1") (pin "33") (pinfunction "MCLK2_33") (pintype "passive+no_connect"))
    )
    (net (code "144") (name "unconnected-(MD1-MISO1-Pad39)") (class "Default")
      (node (ref "MD1") (pin "39") (pinfunction "MISO1_39") (pintype "passive+no_connect"))
    )
    (net (code "145") (name "unconnected-(MD1-MOSI1-Pad26)") (class "Default")
      (node (ref "MD1") (pin "26") (pinfunction "MOSI1_26") (pintype "passive+no_connect"))
    )
    (net (code "146") (name "unconnected-(MD1-OUT1B-Pad32)") (class "Default")
      (node (ref "MD1") (pin "32") (pinfunction "OUT1B_32") (pintype "passive+no_connect"))
    )
    (net (code "147") (name "unconnected-(MD1-OUT1C-Pad9)") (class "Default")
      (node (ref "MD1") (pin "9") (pinfunction "OUT1C_9") (pintype "passive+no_connect"))
    )
    (net (code "148") (name "unconnected-(MD1-RX1-Pad0)") (class "Default")
      (node (ref "MD1") (pin "0") (pinfunction "RX1_0") (pintype "passive+no_connect"))
    )
    (net (code "149") (name "unconnected-(MD1-RX3-Pad15)") (class "Default")
      (node (ref "MD1") (pin "15") (pinfunction "RX3_15") (pintype "passive+no_connect"))
    )
    (net (code "150") (name "unconnected-(MD1-RX4-Pad16)") (class "Default")
      (node (ref "MD1") (pin "16") (pinfunction "RX4_16") (pintype "passive+no_connect"))
    )
    (net (code "151") (name "unconnected-(MD1-RX5-Pad21)") (class "Default")
      (node (ref "MD1") (pin "21") (pinfunction "RX5_21") (pintype "passive+no_connect"))
    )
    (net (code "152") (name "unconnected-(MD1-RX6-Pad25)") (class "Default")
      (node (ref "MD1") (pin "25") (pinfunction "RX6_25") (pintype "passive+no_connect"))
    )
    (net (code "153") (name "unconnected-(MD1-RX7-Pad28)") (class "Default")
      (node (ref "MD1") (pin "28") (pinfunction "RX7_28") (pintype "passive+no_connect"))
    )
    (net (code "154") (name "unconnected-(MD1-RX8-Pad34)") (class "Default")
      (node (ref "MD1") (pin "34") (pinfunction "RX8_34") (pintype "passive"))
    )
    (net (code "155") (name "unconnected-(MD1-SCK1-Pad27)") (class "Default")
      (node (ref "MD1") (pin "27") (pinfunction "SCK1_27") (pintype "passive+no_connect"))
    )
    (net (code "156") (name "unconnected-(MD1-SCL-Pad19)") (class "Default")
      (node (ref "MD1") (pin "19") (pinfunction "SCL_19") (pintype "passive+no_connect"))
    )
    (net (code "157") (name "unconnected-(MD1-SDA-Pad18)") (class "Default")
      (node (ref "MD1") (pin "18") (pinfunction "SDA_18") (pintype "passive+no_connect"))
    )
    (net (code "158") (name "unconnected-(MD1-TX1-Pad1)") (class "Default")
      (node (ref "MD1") (pin "1") (pinfunction "TX1_1") (pintype "passive+no_connect"))
    )
    (net (code "159") (name "unconnected-(MD1-TX2-Pad8)") (class "Default")
      (node (ref "MD1") (pin "8") (pinfunction "TX2_8") (pintype "passive+no_connect"))
    )
    (net (code "160") (name "unconnected-(MD1-TX3-Pad14)") (class "Default")
      (node (ref "MD1") (pin "14") (pinfunction "TX3_14") (pintype "passive+no_connect"))
    )
    (net (code "161") (name "unconnected-(MD1-TX4-Pad17)") (class "Default")
      (node (ref "MD1") (pin "17") (pinfunction "TX4_17") (pintype "passive+no_connect"))
    )
    (net (code "162") (name "unconnected-(MD1-TX5-Pad20)") (class "Default")
      (node (ref "MD1") (pin "20") (pinfunction "TX5_20") (pintype "passive+no_connect"))
    )
    (net (code "163") (name "unconnected-(MD1-TX6-Pad24)") (class "Default")
      (node (ref "MD1") (pin "24") (pinfunction "TX6_24") (pintype "passive+no_connect"))
    )
    (net (code "164") (name "unconnected-(MD1-TX7-Pad29)") (class "Default")
      (node (ref "MD1") (pin "29") (pinfunction "TX7_29") (pintype "passive+no_connect"))
    )
    (net (code "165") (name "unconnected-(MD1-TX8-Pad35)") (class "Default")
      (node (ref "MD1") (pin "35") (pinfunction "TX8_35") (pintype "passive+no_connect"))
    )
    (net (code "166") (name "unconnected-(R1-Pad2)") (class "Default")
      (node (ref "R1") (pin "2") (pinfunction "2_2") (pintype "passive"))
    )
    (net (code "167") (name "unconnected-(R2-Pad1)") (class "Default")
      (node (ref "R2") (pin "1") (pinfunction "1_1") (pintype "passive"))
    )
    (net (code "168") (name "unconnected-(U10-Q7S-Pad9)") (class "Default")
      (node (ref "U10") (pin "9") (pinfunction "Q7S_9") (pintype "output+no_connect"))
    )
  )
)
